# Amplifier.net
KiCad netlist of a schematic drawn in Altium Designer
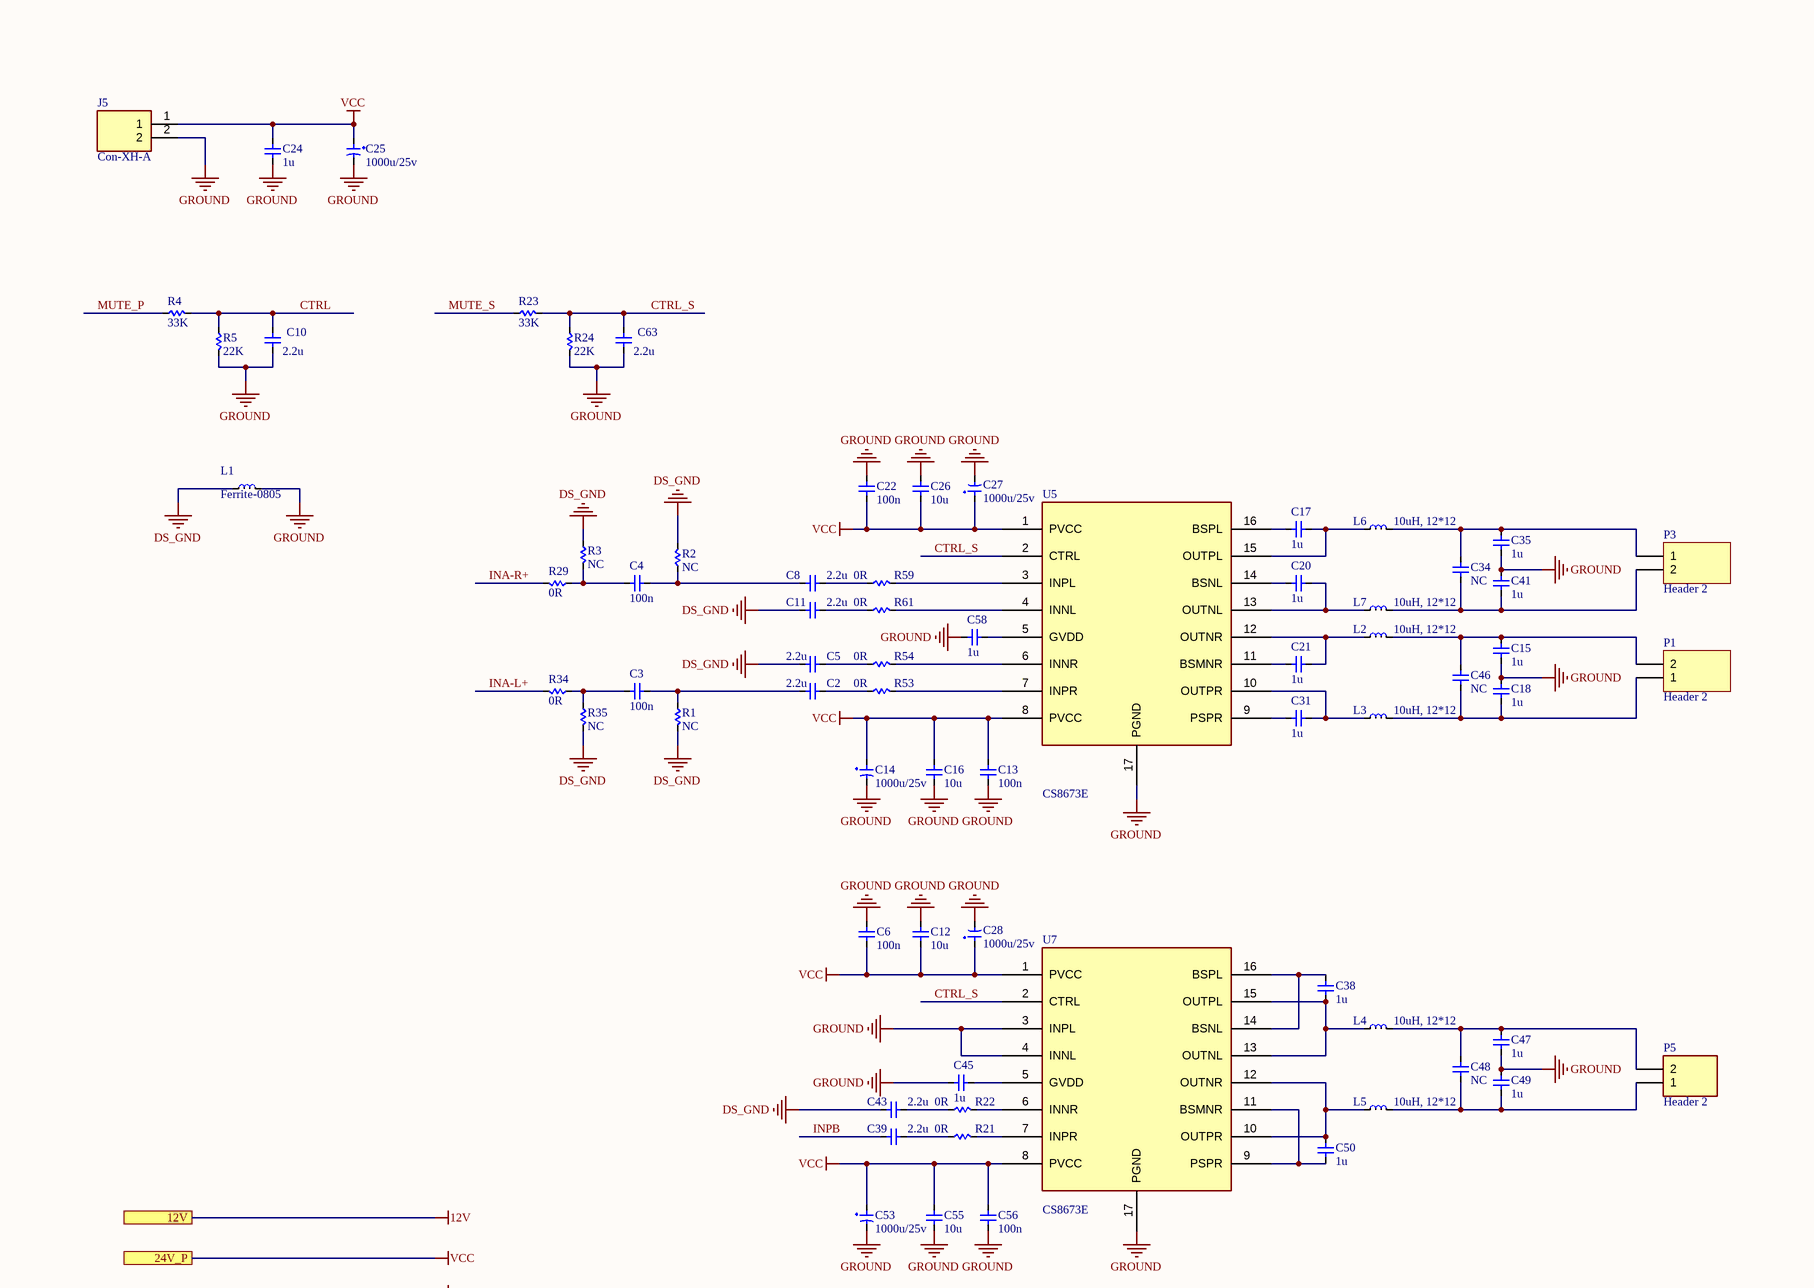
[diagram p0: Amplifier.SchDoc, top left]
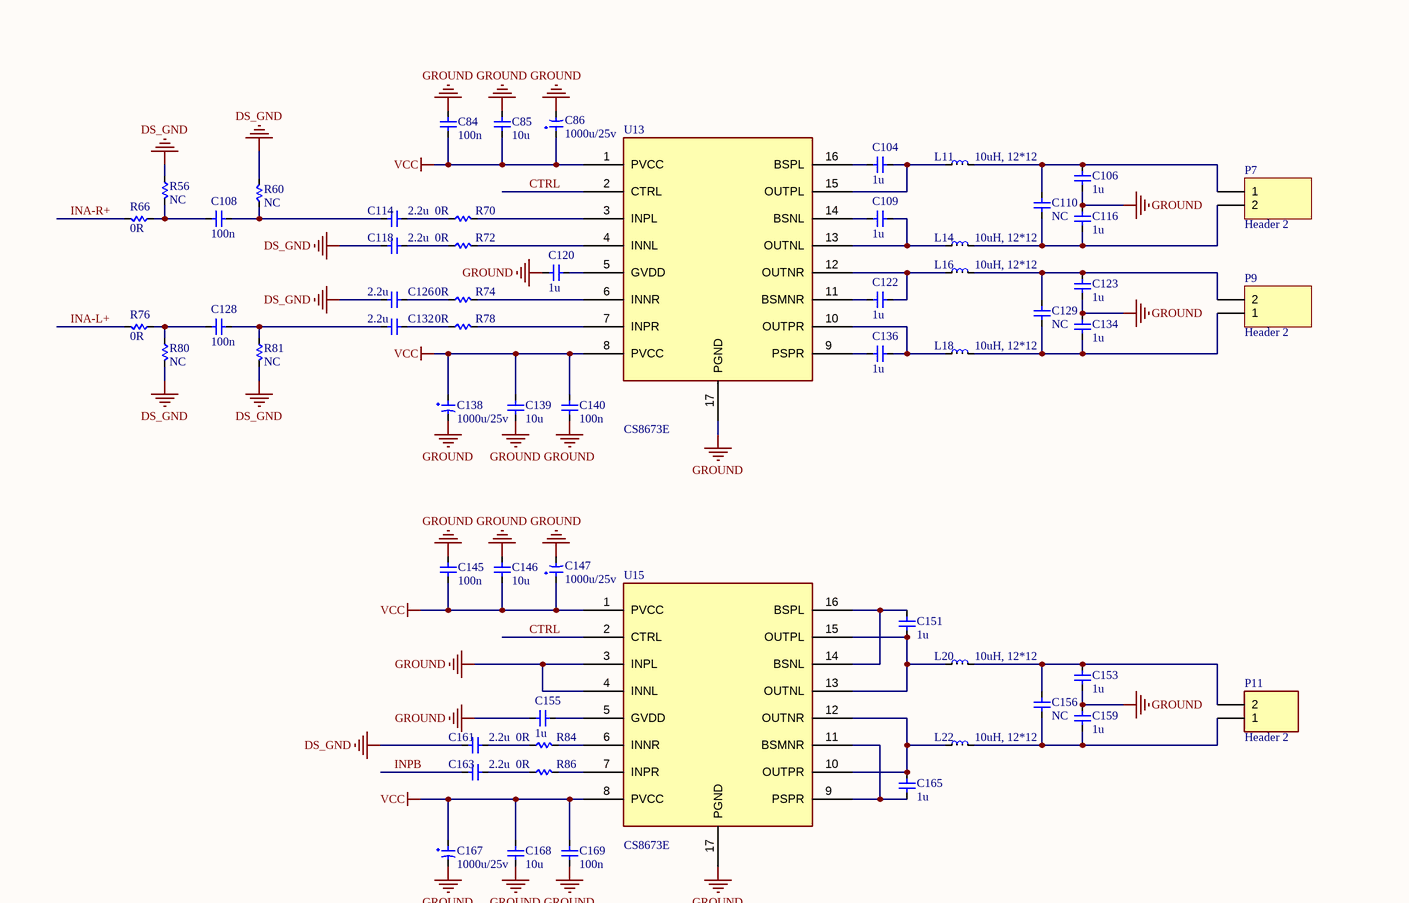
[diagram p1: Amplifier.SchDoc, top middle]
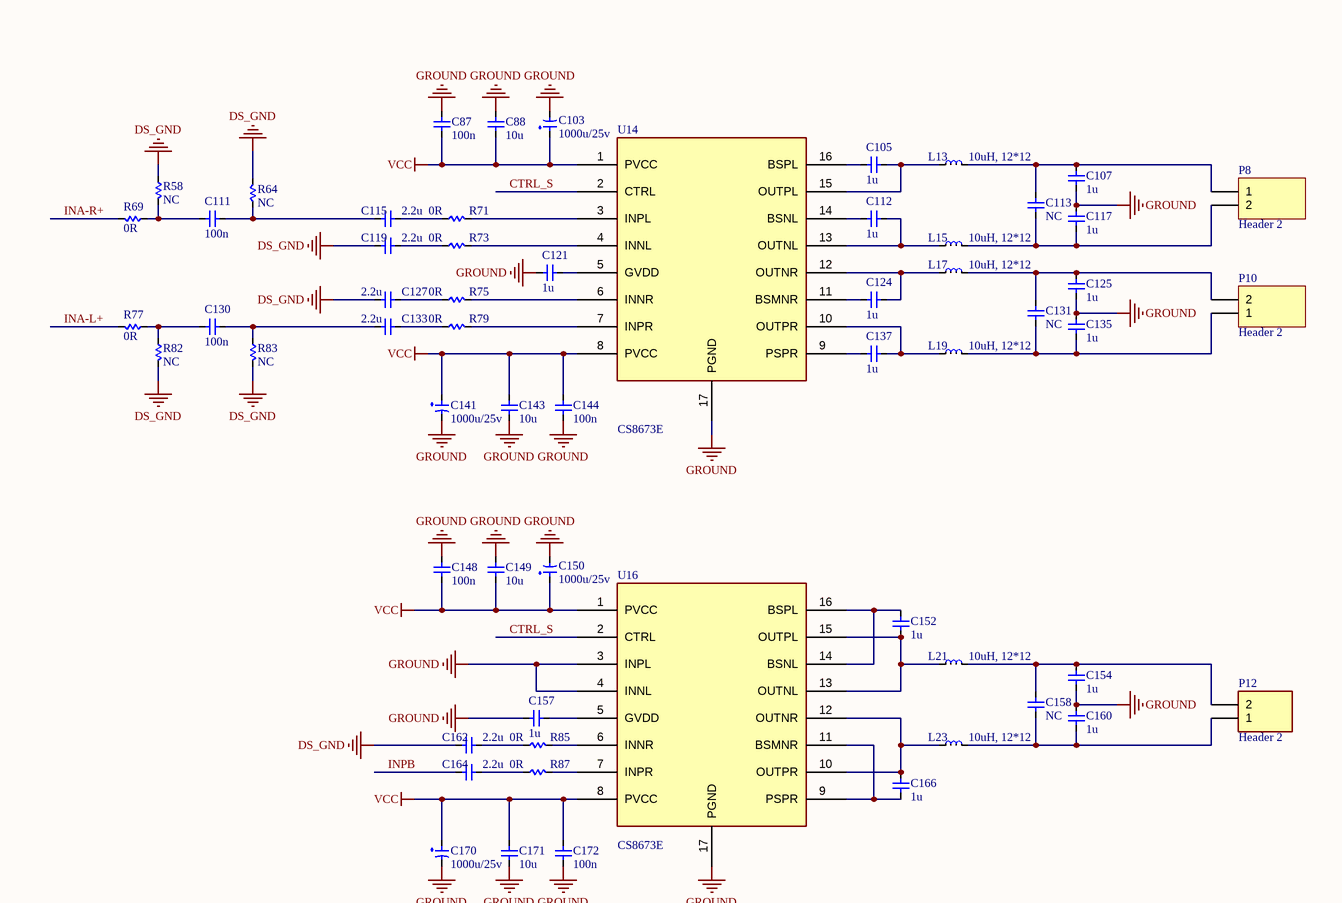
[diagram p2: Amplifier.SchDoc, top right]
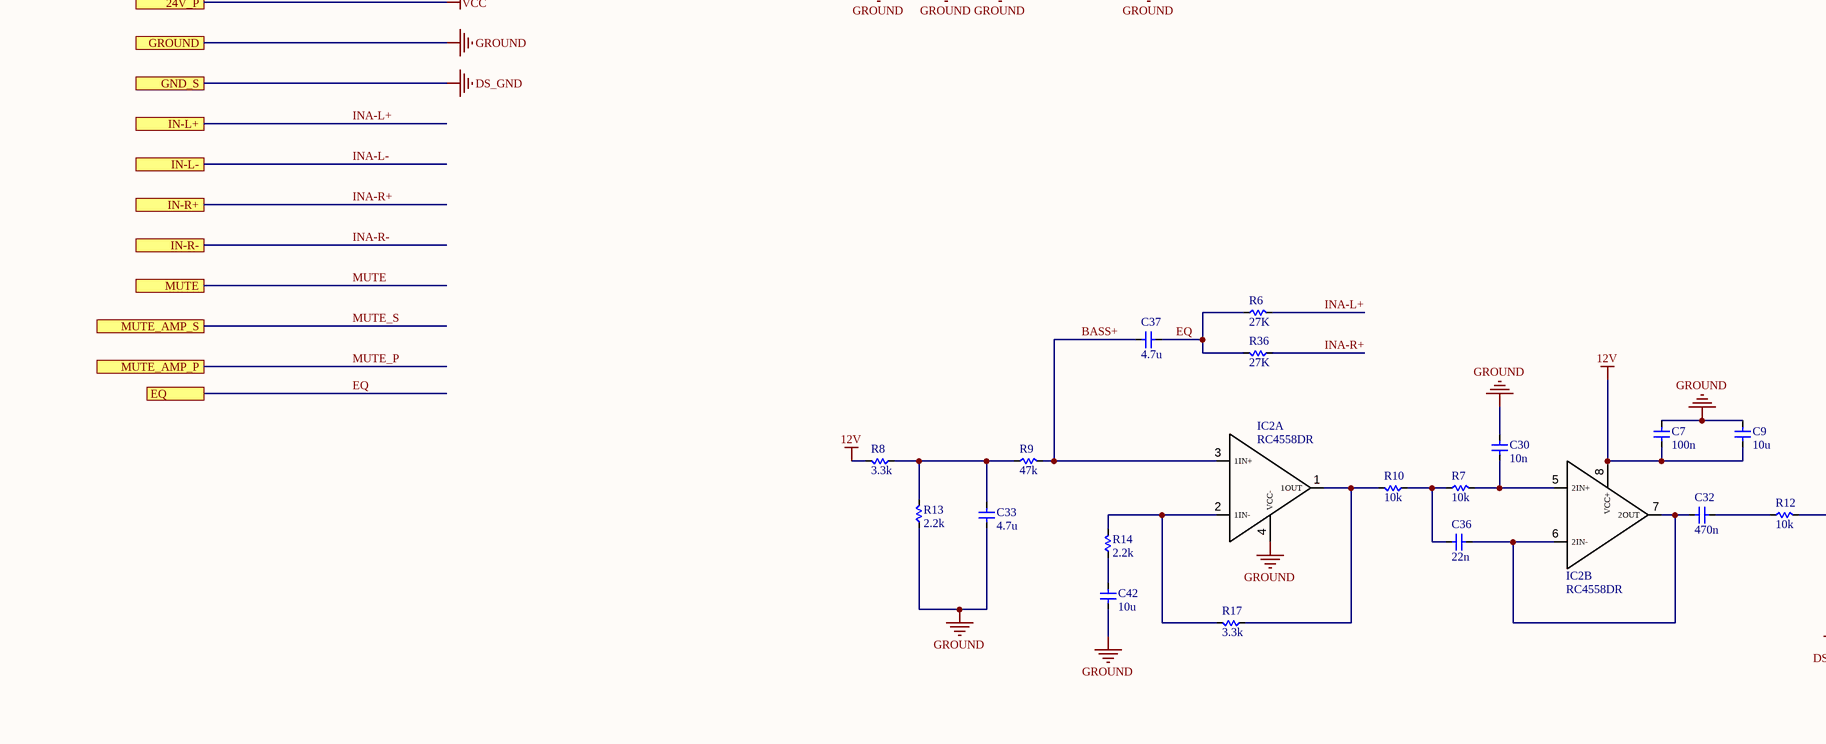
[diagram p3: Amplifier.SchDoc, bottom left]
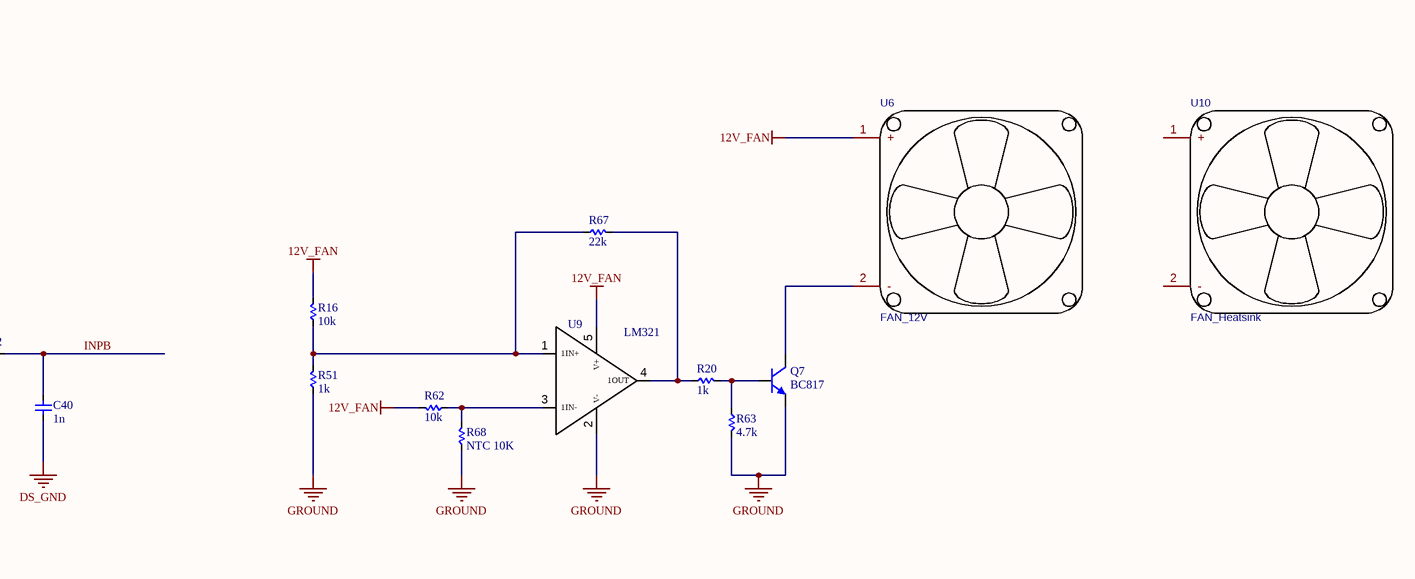
[diagram p4: Amplifier.SchDoc, bottom middle]

(export (version "E")
  (design (tool "Eeschema 10.0.6"))
  (components
    (comp (ref "C2")
      (value "2.2u")
      (footprint "cap0603")
      (description "Capacitor 0603")
      (fields (field (name "PUBLISHER") "Altium Limited"))
      (libsource (lib "mylib1") (part "Cap 0603"))
    )
    (comp (ref "C3")
      (value "100n")
      (footprint "cap0603")
      (description "Capacitor 0603")
      (fields (field (name "PUBLISHER") "Altium Limited"))
      (libsource (lib "mylib") (part "Cap 0603"))
    )
    (comp (ref "C4")
      (value "100n")
      (footprint "cap0603")
      (description "Capacitor 0603")
      (fields (field (name "PUBLISHER") "Altium Limited"))
      (libsource (lib "mylib") (part "Cap 0603"))
    )
    (comp (ref "C5")
      (value "2.2u")
      (footprint "cap0603")
      (description "Capacitor 0603")
      (fields (field (name "PUBLISHER") "Altium Limited"))
      (libsource (lib "mylib1") (part "Cap 0603"))
    )
    (comp (ref "C6")
      (value "100n")
      (footprint "cap0603")
      (description "Capacitor 0603")
      (fields (field (name "PUBLISHER") "Altium Limited"))
      (libsource (lib "mylib1") (part "Cap 0603"))
    )
    (comp (ref "C7")
      (value "100n")
      (footprint "cap0603")
      (description "Capacitor 0603")
      (fields (field (name "PUBLISHER") "Altium Limited"))
      (libsource (lib "mylib1") (part "Cap 0603"))
    )
    (comp (ref "C8")
      (value "2.2u")
      (footprint "cap0603")
      (description "Capacitor 0603")
      (fields (field (name "PUBLISHER") "Altium Limited"))
      (libsource (lib "mylib1") (part "Cap 0603"))
    )
    (comp (ref "C9")
      (value "10u")
      (footprint "cap0603")
      (description "Capacitor 0603")
      (fields (field (name "PUBLISHER") "Altium Limited"))
      (libsource (lib "mylib") (part "Cap 0603"))
    )
    (comp (ref "C10")
      (value "2.2u")
      (footprint "cap0603")
      (description "Capacitor 0603")
      (fields (field (name "PUBLISHER") "Altium Limited"))
      (libsource (lib "mylib") (part "Cap 0603"))
    )
    (comp (ref "C11")
      (value "2.2u")
      (footprint "cap0603")
      (description "Capacitor 0603")
      (fields (field (name "PUBLISHER") "Altium Limited"))
      (libsource (lib "mylib1") (part "Cap 0603"))
    )
    (comp (ref "C12")
      (value "10u")
      (footprint "CAP 0805")
      (description "Capacitor 0805")
      (fields (field (name "PUBLISHER") "Altium Limited"))
      (libsource (lib "Amin-Library") (part "Cap 0805"))
    )
    (comp (ref "C13")
      (value "100n")
      (footprint "cap0603")
      (description "Capacitor 0603")
      (fields (field (name "PUBLISHER") "Altium Limited"))
      (libsource (lib "mylib1") (part "Cap 0603"))
    )
    (comp (ref "C14")
      (value "1000u/25v")
      (footprint "CAP DIP 10*13")
      (description "2200ÂµF 50V Aluminum Electrolytic Capacitors Radial, Can 1000 Hrs @ 105Â°C")
      (fields (field (name "MF") "Nichicon") (field (name "MP") "UVZ1H222MHD"))
      (libsource (lib "") (part "capacitor dip 10*13_1"))
    )
    (comp (ref "C15")
      (value "1u")
      (footprint "CAP 0805")
      (description "Capacitor 0805")
      (fields (field (name "PUBLISHER") "Altium Limited"))
      (libsource (lib "Amin-Library") (part "Cap 0805"))
    )
    (comp (ref "C16")
      (value "10u")
      (footprint "CAP 0805")
      (description "Capacitor 0805")
      (fields (field (name "PUBLISHER") "Altium Limited"))
      (libsource (lib "Amin-Library") (part "Cap 0805"))
    )
    (comp (ref "C17")
      (value "1u")
      (footprint "CAP 0805")
      (description "Capacitor 0805")
      (fields (field (name "PUBLISHER") "Altium Limited"))
      (libsource (lib "Amin-Library") (part "Cap 0805"))
    )
    (comp (ref "C18")
      (value "1u")
      (footprint "CAP 0805")
      (description "Capacitor 0805")
      (fields (field (name "PUBLISHER") "Altium Limited"))
      (libsource (lib "Amin-Library") (part "Cap 0805"))
    )
    (comp (ref "C20")
      (value "1u")
      (footprint "CAP 0805")
      (description "Capacitor 0805")
      (fields (field (name "PUBLISHER") "Altium Limited"))
      (libsource (lib "Amin-Library") (part "Cap 0805"))
    )
    (comp (ref "C21")
      (value "1u")
      (footprint "CAP 0805")
      (description "Capacitor 0805")
      (fields (field (name "PUBLISHER") "Altium Limited"))
      (libsource (lib "Amin-Library") (part "Cap 0805"))
    )
    (comp (ref "C22")
      (value "100n")
      (footprint "cap0603")
      (description "Capacitor 0603")
      (fields (field (name "PUBLISHER") "Altium Limited"))
      (libsource (lib "mylib1") (part "Cap 0603"))
    )
    (comp (ref "C24")
      (value "1u")
      (footprint "cap0603")
      (description "Capacitor 0603")
      (fields (field (name "PUBLISHER") "Altium Limited"))
      (libsource (lib "mylib1") (part "Cap 0603"))
    )
    (comp (ref "C25")
      (value "1000u/25v")
      (footprint "CAP DIP 10*13")
      (description "2200ÂµF 50V Aluminum Electrolytic Capacitors Radial, Can 1000 Hrs @ 105Â°C")
      (fields (field (name "MF") "Nichicon") (field (name "MP") "UVZ1H222MHD"))
      (libsource (lib "") (part "capacitor dip 10*13_2"))
    )
    (comp (ref "C26")
      (value "10u")
      (footprint "CAP 0805")
      (description "Capacitor 0805")
      (fields (field (name "PUBLISHER") "Altium Limited"))
      (libsource (lib "Amin-Library") (part "Cap 0805"))
    )
    (comp (ref "C27")
      (value "1000u/25v")
      (footprint "CAP DIP 10*13")
      (description "2200ÂµF 50V Aluminum Electrolytic Capacitors Radial, Can 1000 Hrs @ 105Â°C")
      (fields (field (name "MF") "Nichicon") (field (name "MP") "UVZ1H222MHD"))
      (libsource (lib "mylib1") (part "capacitor dip 10*13"))
    )
    (comp (ref "C28")
      (value "1000u/25v")
      (footprint "CAP DIP 10*13")
      (description "2200ÂµF 50V Aluminum Electrolytic Capacitors Radial, Can 1000 Hrs @ 105Â°C")
      (fields (field (name "MF") "Nichicon") (field (name "MP") "UVZ1H222MHD"))
      (libsource (lib "mylib1") (part "capacitor dip 10*13"))
    )
    (comp (ref "C30")
      (value "10n")
      (footprint "cap0603")
      (description "Capacitor 0603")
      (fields (field (name "PUBLISHER") "Altium Limited"))
      (libsource (lib "mylib1") (part "Cap 0603"))
    )
    (comp (ref "C31")
      (value "1u")
      (footprint "CAP 0805")
      (description "Capacitor 0805")
      (fields (field (name "PUBLISHER") "Altium Limited"))
      (libsource (lib "Amin-Library") (part "Cap 0805"))
    )
    (comp (ref "C32")
      (value "470n")
      (footprint "cap0603")
      (description "Capacitor 0603")
      (fields (field (name "PUBLISHER") "Altium Limited"))
      (libsource (lib "mylib1") (part "Cap 0603"))
    )
    (comp (ref "C33")
      (value "4.7u")
      (footprint "cap0603")
      (description "Capacitor 0603")
      (fields (field (name "PUBLISHER") "Altium Limited"))
      (libsource (lib "mylib") (part "Cap 0603"))
    )
    (comp (ref "C34")
      (value "NC")
      (footprint "CAP 0805")
      (description "Capacitor 0805")
      (fields (field (name "PUBLISHER") "Altium Limited"))
      (libsource (lib "Amin-Library") (part "Cap 0805"))
    )
    (comp (ref "C35")
      (value "1u")
      (footprint "CAP 0805")
      (description "Capacitor 0805")
      (fields (field (name "PUBLISHER") "Altium Limited"))
      (libsource (lib "Amin-Library") (part "Cap 0805"))
    )
    (comp (ref "C36")
      (value "22n")
      (footprint "cap0603")
      (description "Capacitor 0603")
      (fields (field (name "PUBLISHER") "Altium Limited"))
      (libsource (lib "mylib1") (part "Cap 0603"))
    )
    (comp (ref "C37")
      (value "4.7u")
      (footprint "cap0603")
      (description "Capacitor 0603")
      (fields (field (name "PUBLISHER") "Altium Limited"))
      (libsource (lib "mylib") (part "Cap 0603"))
    )
    (comp (ref "C38")
      (value "1u")
      (footprint "CAP 0805")
      (description "Capacitor 0805")
      (fields (field (name "PUBLISHER") "Altium Limited"))
      (libsource (lib "Amin-Library") (part "Cap 0805"))
    )
    (comp (ref "C39")
      (value "2.2u")
      (footprint "cap0603")
      (description "Capacitor 0603")
      (fields (field (name "PUBLISHER") "Altium Limited"))
      (libsource (lib "mylib1") (part "Cap 0603"))
    )
    (comp (ref "C40")
      (value "1n")
      (footprint "cap0603")
      (description "Capacitor 0603")
      (fields (field (name "PUBLISHER") "Altium Limited"))
      (libsource (lib "mylib1") (part "Cap 0603"))
    )
    (comp (ref "C41")
      (value "1u")
      (footprint "CAP 0805")
      (description "Capacitor 0805")
      (fields (field (name "PUBLISHER") "Altium Limited"))
      (libsource (lib "Amin-Library") (part "Cap 0805"))
    )
    (comp (ref "C42")
      (value "10u")
      (footprint "CAP 1206")
      (description "Capacitor 1206")
      (fields (field (name "PUBLISHER") "Altium Limited"))
      (libsource (lib "mylib") (part "Cap 1206"))
    )
    (comp (ref "C43")
      (value "2.2u")
      (footprint "cap0603")
      (description "Capacitor 0603")
      (fields (field (name "PUBLISHER") "Altium Limited"))
      (libsource (lib "mylib1") (part "Cap 0603"))
    )
    (comp (ref "C45")
      (value "1u")
      (footprint "cap0603")
      (description "Capacitor 0603")
      (fields (field (name "PUBLISHER") "Altium Limited"))
      (libsource (lib "mylib1") (part "Cap 0603"))
    )
    (comp (ref "C46")
      (value "NC")
      (footprint "CAP 0805")
      (description "Capacitor 0805")
      (fields (field (name "PUBLISHER") "Altium Limited"))
      (libsource (lib "Amin-Library") (part "Cap 0805"))
    )
    (comp (ref "C47")
      (value "1u")
      (footprint "CAP 0805")
      (description "Capacitor 0805")
      (fields (field (name "PUBLISHER") "Altium Limited"))
      (libsource (lib "Amin-Library") (part "Cap 0805"))
    )
    (comp (ref "C48")
      (value "NC")
      (footprint "CAP 0805")
      (description "Capacitor 0805")
      (fields (field (name "PUBLISHER") "Altium Limited"))
      (libsource (lib "Amin-Library") (part "Cap 0805"))
    )
    (comp (ref "C49")
      (value "1u")
      (footprint "CAP 0805")
      (description "Capacitor 0805")
      (fields (field (name "PUBLISHER") "Altium Limited"))
      (libsource (lib "Amin-Library") (part "Cap 0805"))
    )
    (comp (ref "C50")
      (value "1u")
      (footprint "CAP 0805")
      (description "Capacitor 0805")
      (fields (field (name "PUBLISHER") "Altium Limited"))
      (libsource (lib "Amin-Library") (part "Cap 0805"))
    )
    (comp (ref "C53")
      (value "1000u/25v")
      (footprint "CAP DIP 10*13")
      (description "2200ÂµF 50V Aluminum Electrolytic Capacitors Radial, Can 1000 Hrs @ 105Â°C")
      (fields (field (name "MF") "Nichicon") (field (name "MP") "UVZ1H222MHD"))
      (libsource (lib "") (part "capacitor dip 10*13_1"))
    )
    (comp (ref "C55")
      (value "10u")
      (footprint "CAP 0805")
      (description "Capacitor 0805")
      (fields (field (name "PUBLISHER") "Altium Limited"))
      (libsource (lib "Amin-Library") (part "Cap 0805"))
    )
    (comp (ref "C56")
      (value "100n")
      (footprint "cap0603")
      (description "Capacitor 0603")
      (fields (field (name "PUBLISHER") "Altium Limited"))
      (libsource (lib "mylib1") (part "Cap 0603"))
    )
    (comp (ref "C58")
      (value "1u")
      (footprint "cap0603")
      (description "Capacitor 0603")
      (fields (field (name "PUBLISHER") "Altium Limited"))
      (libsource (lib "mylib1") (part "Cap 0603"))
    )
    (comp (ref "C63")
      (value "2.2u")
      (footprint "cap0603")
      (description "Capacitor 0603")
      (fields (field (name "PUBLISHER") "Altium Limited"))
      (libsource (lib "mylib") (part "Cap 0603"))
    )
    (comp (ref "C84")
      (value "100n")
      (footprint "cap0603")
      (description "Capacitor 0603")
      (fields (field (name "PUBLISHER") "Altium Limited"))
      (libsource (lib "mylib1") (part "Cap 0603"))
    )
    (comp (ref "C85")
      (value "10u")
      (footprint "CAP 0805")
      (description "Capacitor 0805")
      (fields (field (name "PUBLISHER") "Altium Limited"))
      (libsource (lib "Amin-Library") (part "Cap 0805"))
    )
    (comp (ref "C86")
      (value "1000u/25v")
      (footprint "CAP DIP 10*13")
      (description "2200ÂµF 50V Aluminum Electrolytic Capacitors Radial, Can 1000 Hrs @ 105Â°C")
      (fields (field (name "MF") "Nichicon") (field (name "MP") "UVZ1H222MHD"))
      (libsource (lib "mylib1") (part "capacitor dip 10*13"))
    )
    (comp (ref "C87")
      (value "100n")
      (footprint "cap0603")
      (description "Capacitor 0603")
      (fields (field (name "PUBLISHER") "Altium Limited"))
      (libsource (lib "mylib1") (part "Cap 0603"))
    )
    (comp (ref "C88")
      (value "10u")
      (footprint "CAP 0805")
      (description "Capacitor 0805")
      (fields (field (name "PUBLISHER") "Altium Limited"))
      (libsource (lib "Amin-Library") (part "Cap 0805"))
    )
    (comp (ref "C103")
      (value "1000u/25v")
      (footprint "CAP DIP 10*13")
      (description "2200ÂµF 50V Aluminum Electrolytic Capacitors Radial, Can 1000 Hrs @ 105Â°C")
      (fields (field (name "MF") "Nichicon") (field (name "MP") "UVZ1H222MHD"))
      (libsource (lib "mylib1") (part "capacitor dip 10*13"))
    )
    (comp (ref "C104")
      (value "1u")
      (footprint "CAP 0805")
      (description "Capacitor 0805")
      (fields (field (name "PUBLISHER") "Altium Limited"))
      (libsource (lib "Amin-Library") (part "Cap 0805"))
    )
    (comp (ref "C105")
      (value "1u")
      (footprint "CAP 0805")
      (description "Capacitor 0805")
      (fields (field (name "PUBLISHER") "Altium Limited"))
      (libsource (lib "Amin-Library") (part "Cap 0805"))
    )
    (comp (ref "C106")
      (value "1u")
      (footprint "CAP 0805")
      (description "Capacitor 0805")
      (fields (field (name "PUBLISHER") "Altium Limited"))
      (libsource (lib "Amin-Library") (part "Cap 0805"))
    )
    (comp (ref "C107")
      (value "1u")
      (footprint "CAP 0805")
      (description "Capacitor 0805")
      (fields (field (name "PUBLISHER") "Altium Limited"))
      (libsource (lib "Amin-Library") (part "Cap 0805"))
    )
    (comp (ref "C108")
      (value "100n")
      (footprint "cap0603")
      (description "Capacitor 0603")
      (fields (field (name "PUBLISHER") "Altium Limited"))
      (libsource (lib "mylib") (part "Cap 0603"))
    )
    (comp (ref "C109")
      (value "1u")
      (footprint "CAP 0805")
      (description "Capacitor 0805")
      (fields (field (name "PUBLISHER") "Altium Limited"))
      (libsource (lib "Amin-Library") (part "Cap 0805"))
    )
    (comp (ref "C110")
      (value "NC")
      (footprint "CAP 0805")
      (description "Capacitor 0805")
      (fields (field (name "PUBLISHER") "Altium Limited"))
      (libsource (lib "Amin-Library") (part "Cap 0805"))
    )
    (comp (ref "C111")
      (value "100n")
      (footprint "cap0603")
      (description "Capacitor 0603")
      (fields (field (name "PUBLISHER") "Altium Limited"))
      (libsource (lib "mylib") (part "Cap 0603"))
    )
    (comp (ref "C112")
      (value "1u")
      (footprint "CAP 0805")
      (description "Capacitor 0805")
      (fields (field (name "PUBLISHER") "Altium Limited"))
      (libsource (lib "Amin-Library") (part "Cap 0805"))
    )
    (comp (ref "C113")
      (value "NC")
      (footprint "CAP 0805")
      (description "Capacitor 0805")
      (fields (field (name "PUBLISHER") "Altium Limited"))
      (libsource (lib "Amin-Library") (part "Cap 0805"))
    )
    (comp (ref "C114")
      (value "2.2u")
      (footprint "cap0603")
      (description "Capacitor 0603")
      (fields (field (name "PUBLISHER") "Altium Limited"))
      (libsource (lib "mylib1") (part "Cap 0603"))
    )
    (comp (ref "C115")
      (value "2.2u")
      (footprint "cap0603")
      (description "Capacitor 0603")
      (fields (field (name "PUBLISHER") "Altium Limited"))
      (libsource (lib "mylib1") (part "Cap 0603"))
    )
    (comp (ref "C116")
      (value "1u")
      (footprint "CAP 0805")
      (description "Capacitor 0805")
      (fields (field (name "PUBLISHER") "Altium Limited"))
      (libsource (lib "Amin-Library") (part "Cap 0805"))
    )
    (comp (ref "C117")
      (value "1u")
      (footprint "CAP 0805")
      (description "Capacitor 0805")
      (fields (field (name "PUBLISHER") "Altium Limited"))
      (libsource (lib "Amin-Library") (part "Cap 0805"))
    )
    (comp (ref "C118")
      (value "2.2u")
      (footprint "cap0603")
      (description "Capacitor 0603")
      (fields (field (name "PUBLISHER") "Altium Limited"))
      (libsource (lib "mylib1") (part "Cap 0603"))
    )
    (comp (ref "C119")
      (value "2.2u")
      (footprint "cap0603")
      (description "Capacitor 0603")
      (fields (field (name "PUBLISHER") "Altium Limited"))
      (libsource (lib "mylib1") (part "Cap 0603"))
    )
    (comp (ref "C120")
      (value "1u")
      (footprint "cap0603")
      (description "Capacitor 0603")
      (fields (field (name "PUBLISHER") "Altium Limited"))
      (libsource (lib "mylib1") (part "Cap 0603"))
    )
    (comp (ref "C121")
      (value "1u")
      (footprint "cap0603")
      (description "Capacitor 0603")
      (fields (field (name "PUBLISHER") "Altium Limited"))
      (libsource (lib "mylib1") (part "Cap 0603"))
    )
    (comp (ref "C122")
      (value "1u")
      (footprint "CAP 0805")
      (description "Capacitor 0805")
      (fields (field (name "PUBLISHER") "Altium Limited"))
      (libsource (lib "Amin-Library") (part "Cap 0805"))
    )
    (comp (ref "C123")
      (value "1u")
      (footprint "CAP 0805")
      (description "Capacitor 0805")
      (fields (field (name "PUBLISHER") "Altium Limited"))
      (libsource (lib "Amin-Library") (part "Cap 0805"))
    )
    (comp (ref "C124")
      (value "1u")
      (footprint "CAP 0805")
      (description "Capacitor 0805")
      (fields (field (name "PUBLISHER") "Altium Limited"))
      (libsource (lib "Amin-Library") (part "Cap 0805"))
    )
    (comp (ref "C125")
      (value "1u")
      (footprint "CAP 0805")
      (description "Capacitor 0805")
      (fields (field (name "PUBLISHER") "Altium Limited"))
      (libsource (lib "Amin-Library") (part "Cap 0805"))
    )
    (comp (ref "C126")
      (value "2.2u")
      (footprint "cap0603")
      (description "Capacitor 0603")
      (fields (field (name "PUBLISHER") "Altium Limited"))
      (libsource (lib "mylib1") (part "Cap 0603"))
    )
    (comp (ref "C127")
      (value "2.2u")
      (footprint "cap0603")
      (description "Capacitor 0603")
      (fields (field (name "PUBLISHER") "Altium Limited"))
      (libsource (lib "mylib1") (part "Cap 0603"))
    )
    (comp (ref "C128")
      (value "100n")
      (footprint "cap0603")
      (description "Capacitor 0603")
      (fields (field (name "PUBLISHER") "Altium Limited"))
      (libsource (lib "mylib") (part "Cap 0603"))
    )
    (comp (ref "C129")
      (value "NC")
      (footprint "CAP 0805")
      (description "Capacitor 0805")
      (fields (field (name "PUBLISHER") "Altium Limited"))
      (libsource (lib "Amin-Library") (part "Cap 0805"))
    )
    (comp (ref "C130")
      (value "100n")
      (footprint "cap0603")
      (description "Capacitor 0603")
      (fields (field (name "PUBLISHER") "Altium Limited"))
      (libsource (lib "mylib") (part "Cap 0603"))
    )
    (comp (ref "C131")
      (value "NC")
      (footprint "CAP 0805")
      (description "Capacitor 0805")
      (fields (field (name "PUBLISHER") "Altium Limited"))
      (libsource (lib "Amin-Library") (part "Cap 0805"))
    )
    (comp (ref "C132")
      (value "2.2u")
      (footprint "cap0603")
      (description "Capacitor 0603")
      (fields (field (name "PUBLISHER") "Altium Limited"))
      (libsource (lib "mylib1") (part "Cap 0603"))
    )
    (comp (ref "C133")
      (value "2.2u")
      (footprint "cap0603")
      (description "Capacitor 0603")
      (fields (field (name "PUBLISHER") "Altium Limited"))
      (libsource (lib "mylib1") (part "Cap 0603"))
    )
    (comp (ref "C134")
      (value "1u")
      (footprint "CAP 0805")
      (description "Capacitor 0805")
      (fields (field (name "PUBLISHER") "Altium Limited"))
      (libsource (lib "Amin-Library") (part "Cap 0805"))
    )
    (comp (ref "C135")
      (value "1u")
      (footprint "CAP 0805")
      (description "Capacitor 0805")
      (fields (field (name "PUBLISHER") "Altium Limited"))
      (libsource (lib "Amin-Library") (part "Cap 0805"))
    )
    (comp (ref "C136")
      (value "1u")
      (footprint "CAP 0805")
      (description "Capacitor 0805")
      (fields (field (name "PUBLISHER") "Altium Limited"))
      (libsource (lib "Amin-Library") (part "Cap 0805"))
    )
    (comp (ref "C137")
      (value "1u")
      (footprint "CAP 0805")
      (description "Capacitor 0805")
      (fields (field (name "PUBLISHER") "Altium Limited"))
      (libsource (lib "Amin-Library") (part "Cap 0805"))
    )
    (comp (ref "C138")
      (value "1000u/25v")
      (footprint "CAP DIP 10*13")
      (description "2200ÂµF 50V Aluminum Electrolytic Capacitors Radial, Can 1000 Hrs @ 105Â°C")
      (fields (field (name "MF") "Nichicon") (field (name "MP") "UVZ1H222MHD"))
      (libsource (lib "") (part "capacitor dip 10*13_1"))
    )
    (comp (ref "C139")
      (value "10u")
      (footprint "CAP 0805")
      (description "Capacitor 0805")
      (fields (field (name "PUBLISHER") "Altium Limited"))
      (libsource (lib "Amin-Library") (part "Cap 0805"))
    )
    (comp (ref "C140")
      (value "100n")
      (footprint "cap0603")
      (description "Capacitor 0603")
      (fields (field (name "PUBLISHER") "Altium Limited"))
      (libsource (lib "mylib1") (part "Cap 0603"))
    )
    (comp (ref "C141")
      (value "1000u/25v")
      (footprint "CAP DIP 10*13")
      (description "2200ÂµF 50V Aluminum Electrolytic Capacitors Radial, Can 1000 Hrs @ 105Â°C")
      (fields (field (name "MF") "Nichicon") (field (name "MP") "UVZ1H222MHD"))
      (libsource (lib "") (part "capacitor dip 10*13_1"))
    )
    (comp (ref "C143")
      (value "10u")
      (footprint "CAP 0805")
      (description "Capacitor 0805")
      (fields (field (name "PUBLISHER") "Altium Limited"))
      (libsource (lib "Amin-Library") (part "Cap 0805"))
    )
    (comp (ref "C144")
      (value "100n")
      (footprint "cap0603")
      (description "Capacitor 0603")
      (fields (field (name "PUBLISHER") "Altium Limited"))
      (libsource (lib "mylib1") (part "Cap 0603"))
    )
    (comp (ref "C145")
      (value "100n")
      (footprint "cap0603")
      (description "Capacitor 0603")
      (fields (field (name "PUBLISHER") "Altium Limited"))
      (libsource (lib "mylib1") (part "Cap 0603"))
    )
    (comp (ref "C146")
      (value "10u")
      (footprint "CAP 0805")
      (description "Capacitor 0805")
      (fields (field (name "PUBLISHER") "Altium Limited"))
      (libsource (lib "Amin-Library") (part "Cap 0805"))
    )
    (comp (ref "C147")
      (value "1000u/25v")
      (footprint "CAP DIP 10*13")
      (description "2200ÂµF 50V Aluminum Electrolytic Capacitors Radial, Can 1000 Hrs @ 105Â°C")
      (fields (field (name "MF") "Nichicon") (field (name "MP") "UVZ1H222MHD"))
      (libsource (lib "mylib1") (part "capacitor dip 10*13"))
    )
    (comp (ref "C148")
      (value "100n")
      (footprint "cap0603")
      (description "Capacitor 0603")
      (fields (field (name "PUBLISHER") "Altium Limited"))
      (libsource (lib "mylib1") (part "Cap 0603"))
    )
    (comp (ref "C149")
      (value "10u")
      (footprint "CAP 0805")
      (description "Capacitor 0805")
      (fields (field (name "PUBLISHER") "Altium Limited"))
      (libsource (lib "Amin-Library") (part "Cap 0805"))
    )
    (comp (ref "C150")
      (value "1000u/25v")
      (footprint "CAP DIP 10*13")
      (description "2200ÂµF 50V Aluminum Electrolytic Capacitors Radial, Can 1000 Hrs @ 105Â°C")
      (fields (field (name "MF") "Nichicon") (field (name "MP") "UVZ1H222MHD"))
      (libsource (lib "mylib1") (part "capacitor dip 10*13"))
    )
    (comp (ref "C151")
      (value "1u")
      (footprint "CAP 0805")
      (description "Capacitor 0805")
      (fields (field (name "PUBLISHER") "Altium Limited"))
      (libsource (lib "Amin-Library") (part "Cap 0805"))
    )
    (comp (ref "C152")
      (value "1u")
      (footprint "CAP 0805")
      (description "Capacitor 0805")
      (fields (field (name "PUBLISHER") "Altium Limited"))
      (libsource (lib "Amin-Library") (part "Cap 0805"))
    )
    (comp (ref "C153")
      (value "1u")
      (footprint "CAP 0805")
      (description "Capacitor 0805")
      (fields (field (name "PUBLISHER") "Altium Limited"))
      (libsource (lib "Amin-Library") (part "Cap 0805"))
    )
    (comp (ref "C154")
      (value "1u")
      (footprint "CAP 0805")
      (description "Capacitor 0805")
      (fields (field (name "PUBLISHER") "Altium Limited"))
      (libsource (lib "Amin-Library") (part "Cap 0805"))
    )
    (comp (ref "C155")
      (value "1u")
      (footprint "cap0603")
      (description "Capacitor 0603")
      (fields (field (name "PUBLISHER") "Altium Limited"))
      (libsource (lib "mylib1") (part "Cap 0603"))
    )
    (comp (ref "C156")
      (value "NC")
      (footprint "CAP 0805")
      (description "Capacitor 0805")
      (fields (field (name "PUBLISHER") "Altium Limited"))
      (libsource (lib "Amin-Library") (part "Cap 0805"))
    )
    (comp (ref "C157")
      (value "1u")
      (footprint "cap0603")
      (description "Capacitor 0603")
      (fields (field (name "PUBLISHER") "Altium Limited"))
      (libsource (lib "mylib1") (part "Cap 0603"))
    )
    (comp (ref "C158")
      (value "NC")
      (footprint "CAP 0805")
      (description "Capacitor 0805")
      (fields (field (name "PUBLISHER") "Altium Limited"))
      (libsource (lib "Amin-Library") (part "Cap 0805"))
    )
    (comp (ref "C159")
      (value "1u")
      (footprint "CAP 0805")
      (description "Capacitor 0805")
      (fields (field (name "PUBLISHER") "Altium Limited"))
      (libsource (lib "Amin-Library") (part "Cap 0805"))
    )
    (comp (ref "C160")
      (value "1u")
      (footprint "CAP 0805")
      (description "Capacitor 0805")
      (fields (field (name "PUBLISHER") "Altium Limited"))
      (libsource (lib "Amin-Library") (part "Cap 0805"))
    )
    (comp (ref "C161")
      (value "2.2u")
      (footprint "cap0603")
      (description "Capacitor 0603")
      (fields (field (name "PUBLISHER") "Altium Limited"))
      (libsource (lib "mylib1") (part "Cap 0603"))
    )
    (comp (ref "C162")
      (value "2.2u")
      (footprint "cap0603")
      (description "Capacitor 0603")
      (fields (field (name "PUBLISHER") "Altium Limited"))
      (libsource (lib "mylib1") (part "Cap 0603"))
    )
    (comp (ref "C163")
      (value "2.2u")
      (footprint "cap0603")
      (description "Capacitor 0603")
      (fields (field (name "PUBLISHER") "Altium Limited"))
      (libsource (lib "mylib1") (part "Cap 0603"))
    )
    (comp (ref "C164")
      (value "2.2u")
      (footprint "cap0603")
      (description "Capacitor 0603")
      (fields (field (name "PUBLISHER") "Altium Limited"))
      (libsource (lib "mylib1") (part "Cap 0603"))
    )
    (comp (ref "C165")
      (value "1u")
      (footprint "CAP 0805")
      (description "Capacitor 0805")
      (fields (field (name "PUBLISHER") "Altium Limited"))
      (libsource (lib "Amin-Library") (part "Cap 0805"))
    )
    (comp (ref "C166")
      (value "1u")
      (footprint "CAP 0805")
      (description "Capacitor 0805")
      (fields (field (name "PUBLISHER") "Altium Limited"))
      (libsource (lib "Amin-Library") (part "Cap 0805"))
    )
    (comp (ref "C167")
      (value "1000u/25v")
      (footprint "CAP DIP 10*13")
      (description "2200ÂµF 50V Aluminum Electrolytic Capacitors Radial, Can 1000 Hrs @ 105Â°C")
      (fields (field (name "MF") "Nichicon") (field (name "MP") "UVZ1H222MHD"))
      (libsource (lib "") (part "capacitor dip 10*13_1"))
    )
    (comp (ref "C168")
      (value "10u")
      (footprint "CAP 0805")
      (description "Capacitor 0805")
      (fields (field (name "PUBLISHER") "Altium Limited"))
      (libsource (lib "Amin-Library") (part "Cap 0805"))
    )
    (comp (ref "C169")
      (value "100n")
      (footprint "cap0603")
      (description "Capacitor 0603")
      (fields (field (name "PUBLISHER") "Altium Limited"))
      (libsource (lib "mylib1") (part "Cap 0603"))
    )
    (comp (ref "C170")
      (value "1000u/25v")
      (footprint "CAP DIP 10*13")
      (description "2200ÂµF 50V Aluminum Electrolytic Capacitors Radial, Can 1000 Hrs @ 105Â°C")
      (fields (field (name "MF") "Nichicon") (field (name "MP") "UVZ1H222MHD"))
      (libsource (lib "") (part "capacitor dip 10*13_1"))
    )
    (comp (ref "C171")
      (value "10u")
      (footprint "CAP 0805")
      (description "Capacitor 0805")
      (fields (field (name "PUBLISHER") "Altium Limited"))
      (libsource (lib "Amin-Library") (part "Cap 0805"))
    )
    (comp (ref "C172")
      (value "100n")
      (footprint "cap0603")
      (description "Capacitor 0603")
      (fields (field (name "PUBLISHER") "Altium Limited"))
      (libsource (lib "mylib1") (part "Cap 0603"))
    )
    (comp (ref "IC2")
      (value "RC4558DR")
      (footprint "RC4558")
      (description "Integrated Circuit SOIC 8")
      (fields (field (name "MOUSER PART NUMBER") "595-RC4558DR"))
      (libsource (lib "STM32F103C8T6") (part "RC4558DR"))
    )
    (comp (ref "J5")
      (value "Con-XH-A")
      (footprint "Con-JST_B2B-XH-A")
      (description "Connector Header Through Hole 2 position 0.098 _2.50mm_")
      (fields (field (name "MP") "B2B-XH-A_LF__SN_") (field (name "MF") "JST Sales"))
      (libsource (lib "Amin-Library") (part "Con-B2B-XH-A"))
    )
    (comp (ref "L1")
      (value "Ferrite-0805")
      (footprint "Ferrite-0805")
      (description "BLM Series 0805 330 Ohm 400 mA 0.58 Ohm DCR Surface Mount Ferrite Bead")
      (fields (field (name "MF") "Murata") (field (name "MP") "BLM18BB331SN1D"))
      (libsource (lib "mylib") (part "Ferrite _0805"))
    )
    (comp (ref "L2")
      (value "10uH, 12*12")
      (footprint "inductor 12*12")
      (description "Inductor round 12*12")
      (fields (field (name "MP") "DR127-330-R") (field (name "MF") "Eaton"))
      (libsource (lib "Amin-Library") (part "INDUCTOR 12*12"))
    )
    (comp (ref "L3")
      (value "10uH, 12*12")
      (footprint "inductor 12*12")
      (description "Inductor round 12*12")
      (fields (field (name "MP") "DR127-330-R") (field (name "MF") "Eaton"))
      (libsource (lib "Amin-Library") (part "INDUCTOR 12*12"))
    )
    (comp (ref "L4")
      (value "10uH, 12*12")
      (footprint "inductor 12*12")
      (description "Inductor round 12*12")
      (fields (field (name "MP") "DR127-330-R") (field (name "MF") "Eaton"))
      (libsource (lib "Amin-Library") (part "INDUCTOR 12*12"))
    )
    (comp (ref "L5")
      (value "10uH, 12*12")
      (footprint "inductor 12*12")
      (description "Inductor round 12*12")
      (fields (field (name "MP") "DR127-330-R") (field (name "MF") "Eaton"))
      (libsource (lib "Amin-Library") (part "INDUCTOR 12*12"))
    )
    (comp (ref "L6")
      (value "10uH, 12*12")
      (footprint "inductor 12*12")
      (description "Inductor round 12*12")
      (fields (field (name "MP") "DR127-330-R") (field (name "MF") "Eaton"))
      (libsource (lib "Amin-Library") (part "INDUCTOR 12*12"))
    )
    (comp (ref "L7")
      (value "10uH, 12*12")
      (footprint "inductor 12*12")
      (description "Inductor round 12*12")
      (fields (field (name "MP") "DR127-330-R") (field (name "MF") "Eaton"))
      (libsource (lib "Amin-Library") (part "INDUCTOR 12*12"))
    )
    (comp (ref "L11")
      (value "10uH, 12*12")
      (footprint "inductor 12*12")
      (description "Inductor round 12*12")
      (fields (field (name "MP") "DR127-330-R") (field (name "MF") "Eaton"))
      (libsource (lib "Amin-Library") (part "INDUCTOR 12*12"))
    )
    (comp (ref "L13")
      (value "10uH, 12*12")
      (footprint "inductor 12*12")
      (description "Inductor round 12*12")
      (fields (field (name "MP") "DR127-330-R") (field (name "MF") "Eaton"))
      (libsource (lib "Amin-Library") (part "INDUCTOR 12*12"))
    )
    (comp (ref "L14")
      (value "10uH, 12*12")
      (footprint "inductor 12*12")
      (description "Inductor round 12*12")
      (fields (field (name "MP") "DR127-330-R") (field (name "MF") "Eaton"))
      (libsource (lib "Amin-Library") (part "INDUCTOR 12*12"))
    )
    (comp (ref "L15")
      (value "10uH, 12*12")
      (footprint "inductor 12*12")
      (description "Inductor round 12*12")
      (fields (field (name "MP") "DR127-330-R") (field (name "MF") "Eaton"))
      (libsource (lib "Amin-Library") (part "INDUCTOR 12*12"))
    )
    (comp (ref "L16")
      (value "10uH, 12*12")
      (footprint "inductor 12*12")
      (description "Inductor round 12*12")
      (fields (field (name "MP") "DR127-330-R") (field (name "MF") "Eaton"))
      (libsource (lib "Amin-Library") (part "INDUCTOR 12*12"))
    )
    (comp (ref "L17")
      (value "10uH, 12*12")
      (footprint "inductor 12*12")
      (description "Inductor round 12*12")
      (fields (field (name "MP") "DR127-330-R") (field (name "MF") "Eaton"))
      (libsource (lib "Amin-Library") (part "INDUCTOR 12*12"))
    )
    (comp (ref "L18")
      (value "10uH, 12*12")
      (footprint "inductor 12*12")
      (description "Inductor round 12*12")
      (fields (field (name "MP") "DR127-330-R") (field (name "MF") "Eaton"))
      (libsource (lib "Amin-Library") (part "INDUCTOR 12*12"))
    )
    (comp (ref "L19")
      (value "10uH, 12*12")
      (footprint "inductor 12*12")
      (description "Inductor round 12*12")
      (fields (field (name "MP") "DR127-330-R") (field (name "MF") "Eaton"))
      (libsource (lib "Amin-Library") (part "INDUCTOR 12*12"))
    )
    (comp (ref "L20")
      (value "10uH, 12*12")
      (footprint "inductor 12*12")
      (description "Inductor round 12*12")
      (fields (field (name "MP") "DR127-330-R") (field (name "MF") "Eaton"))
      (libsource (lib "Amin-Library") (part "INDUCTOR 12*12"))
    )
    (comp (ref "L21")
      (value "10uH, 12*12")
      (footprint "inductor 12*12")
      (description "Inductor round 12*12")
      (fields (field (name "MP") "DR127-330-R") (field (name "MF") "Eaton"))
      (libsource (lib "Amin-Library") (part "INDUCTOR 12*12"))
    )
    (comp (ref "L22")
      (value "10uH, 12*12")
      (footprint "inductor 12*12")
      (description "Inductor round 12*12")
      (fields (field (name "MP") "DR127-330-R") (field (name "MF") "Eaton"))
      (libsource (lib "Amin-Library") (part "INDUCTOR 12*12"))
    )
    (comp (ref "L23")
      (value "10uH, 12*12")
      (footprint "inductor 12*12")
      (description "Inductor round 12*12")
      (fields (field (name "MP") "DR127-330-R") (field (name "MF") "Eaton"))
      (libsource (lib "Amin-Library") (part "INDUCTOR 12*12"))
    )
    (comp (ref "P1")
      (value "Header 2")
      (footprint "CONN-PHOENIX-5.08")
      (description "Phoenix Connector 5.08")
      (fields (field (name "PUBLISHER") "Altium Limited"))
      (libsource (lib "Amin-Library") (part "CONN-Phoenix-5.08"))
    )
    (comp (ref "P3")
      (value "Header 2")
      (footprint "CONN-PHOENIX-5.08")
      (description "Phoenix Connector 5.08")
      (fields (field (name "PUBLISHER") "Altium Limited"))
      (libsource (lib "") (part "CONN-Phoenix-5.08_1"))
    )
    (comp (ref "P5")
      (value "Header 2")
      (footprint "CONN-PHOENIX-3.81")
      (description "Phoenix Connector 3.81")
      (fields (field (name "PUBLISHER") "Altium Limited"))
      (libsource (lib "Amin-Library") (part "CONN-Phoenix-3.81_1"))
    )
    (comp (ref "P7")
      (value "Header 2")
      (footprint "CONN-PHOENIX-5.08")
      (description "Phoenix Connector 5.08")
      (fields (field (name "PUBLISHER") "Altium Limited"))
      (libsource (lib "") (part "CONN-Phoenix-5.08_1"))
    )
    (comp (ref "P8")
      (value "Header 2")
      (footprint "CONN-PHOENIX-5.08")
      (description "Phoenix Connector 5.08")
      (fields (field (name "PUBLISHER") "Altium Limited"))
      (libsource (lib "") (part "CONN-Phoenix-5.08_1"))
    )
    (comp (ref "P9")
      (value "Header 2")
      (footprint "CONN-PHOENIX-5.08")
      (description "Phoenix Connector 5.08")
      (fields (field (name "PUBLISHER") "Altium Limited"))
      (libsource (lib "Amin-Library") (part "CONN-Phoenix-5.08"))
    )
    (comp (ref "P10")
      (value "Header 2")
      (footprint "CONN-PHOENIX-5.08")
      (description "Phoenix Connector 5.08")
      (fields (field (name "PUBLISHER") "Altium Limited"))
      (libsource (lib "Amin-Library") (part "CONN-Phoenix-5.08"))
    )
    (comp (ref "P11")
      (value "Header 2")
      (footprint "CONN-PHOENIX-3.81")
      (description "Phoenix Connector 3.81")
      (fields (field (name "PUBLISHER") "Altium Limited"))
      (libsource (lib "Amin-Library") (part "CONN-Phoenix-3.81_1"))
    )
    (comp (ref "P12")
      (value "Header 2")
      (footprint "CONN-PHOENIX-3.81")
      (description "Phoenix Connector 3.81")
      (fields (field (name "PUBLISHER") "Altium Limited"))
      (libsource (lib "Amin-Library") (part "CONN-Phoenix-3.81_1"))
    )
    (comp (ref "Q7")
      (value "BC817")
      (footprint "BC817")
      (description "NPN General Purpose Amplifier BJT")
      (fields (field (name "PUBLISHER") "Altium Limited"))
      (libsource (lib "Amin-Library") (part "BC817"))
    )
    (comp (ref "R1")
      (value "NC")
      (footprint "RES-0603")
      (description "Resistor 0603")
      (fields (field (name "PUBLISHER") "Altium Limited"))
      (libsource (lib "mylib1") (part "Res 0603"))
    )
    (comp (ref "R2")
      (value "NC")
      (footprint "RES-0603")
      (description "Resistor 0603")
      (fields (field (name "PUBLISHER") "Altium Limited"))
      (libsource (lib "mylib1") (part "Res 0603"))
    )
    (comp (ref "R3")
      (value "NC")
      (footprint "RES-0603")
      (description "Resistor 0603")
      (fields (field (name "PUBLISHER") "Altium Limited"))
      (libsource (lib "mylib1") (part "Res 0603"))
    )
    (comp (ref "R4")
      (value "33K")
      (footprint "RES-0603")
      (description "Resistor 0603")
      (fields (field (name "PUBLISHER") "Altium Limited"))
      (libsource (lib "mylib1") (part "Res 0603"))
    )
    (comp (ref "R5")
      (value "22K")
      (footprint "RES-0603")
      (description "Resistor 0603")
      (fields (field (name "PUBLISHER") "Altium Limited"))
      (libsource (lib "mylib1") (part "Res 0603"))
    )
    (comp (ref "R6")
      (value "27K")
      (footprint "RES-0603")
      (description "Resistor 0603")
      (fields (field (name "PUBLISHER") "Altium Limited"))
      (libsource (lib "mylib1") (part "Res 0603"))
    )
    (comp (ref "R7")
      (value "10k")
      (footprint "RES-0603")
      (description "Resistor 0603")
      (fields (field (name "PUBLISHER") "Altium Limited"))
      (libsource (lib "mylib1") (part "Res 0603"))
    )
    (comp (ref "R8")
      (value "3.3k")
      (footprint "RES-0603")
      (description "Resistor 0603")
      (fields (field (name "PUBLISHER") "Altium Limited"))
      (libsource (lib "mylib1") (part "Res 0603"))
    )
    (comp (ref "R9")
      (value "47k")
      (footprint "RES-0603")
      (description "Resistor 0603")
      (fields (field (name "PUBLISHER") "Altium Limited"))
      (libsource (lib "mylib1") (part "Res 0603"))
    )
    (comp (ref "R10")
      (value "10k")
      (footprint "RES-0603")
      (description "Resistor 0603")
      (fields (field (name "PUBLISHER") "Altium Limited"))
      (libsource (lib "mylib1") (part "Res 0603"))
    )
    (comp (ref "R12")
      (value "10k")
      (footprint "RES-0603")
      (description "Resistor 0603")
      (fields (field (name "PUBLISHER") "Altium Limited"))
      (libsource (lib "mylib1") (part "Res 0603"))
    )
    (comp (ref "R13")
      (value "2.2k")
      (footprint "RES-0603")
      (description "Resistor 0603")
      (fields (field (name "PUBLISHER") "Altium Limited"))
      (libsource (lib "mylib1") (part "Res 0603"))
    )
    (comp (ref "R14")
      (value "2.2k")
      (footprint "RES-0603")
      (description "Resistor 0603")
      (fields (field (name "PUBLISHER") "Altium Limited"))
      (libsource (lib "mylib1") (part "Res 0603"))
    )
    (comp (ref "R16")
      (value "10k")
      (footprint "RES-0603")
      (description "Resistor 0603")
      (fields (field (name "PUBLISHER") "Altium Limited"))
      (libsource (lib "Amin-Library") (part "Res 0603"))
    )
    (comp (ref "R17")
      (value "3.3k")
      (footprint "RES-0603")
      (description "Resistor 0603")
      (fields (field (name "PUBLISHER") "Altium Limited"))
      (libsource (lib "mylib1") (part "Res 0603"))
    )
    (comp (ref "R20")
      (value "1k")
      (footprint "RES-0603")
      (description "Resistor 0603")
      (fields (field (name "PUBLISHER") "Altium Limited"))
      (libsource (lib "Amin-Library") (part "Res 0603"))
    )
    (comp (ref "R21")
      (value "0R")
      (footprint "RES-0603")
      (description "Resistor 0603")
      (fields (field (name "PUBLISHER") "Altium Limited"))
      (libsource (lib "Amin-Library") (part "Res 0603"))
    )
    (comp (ref "R22")
      (value "0R")
      (footprint "RES-0603")
      (description "Resistor 0603")
      (fields (field (name "PUBLISHER") "Altium Limited"))
      (libsource (lib "Amin-Library") (part "Res 0603"))
    )
    (comp (ref "R23")
      (value "33K")
      (footprint "RES-0603")
      (description "Resistor 0603")
      (fields (field (name "PUBLISHER") "Altium Limited"))
      (libsource (lib "mylib1") (part "Res 0603"))
    )
    (comp (ref "R24")
      (value "22K")
      (footprint "RES-0603")
      (description "Resistor 0603")
      (fields (field (name "PUBLISHER") "Altium Limited"))
      (libsource (lib "mylib1") (part "Res 0603"))
    )
    (comp (ref "R29")
      (value "0R")
      (footprint "RES-0603")
      (description "Resistor 0603")
      (fields (field (name "PUBLISHER") "Altium Limited"))
      (libsource (lib "mylib1") (part "Res 0603"))
    )
    (comp (ref "R34")
      (value "0R")
      (footprint "RES-0603")
      (description "Resistor 0603")
      (fields (field (name "PUBLISHER") "Altium Limited"))
      (libsource (lib "mylib1") (part "Res 0603"))
    )
    (comp (ref "R35")
      (value "NC")
      (footprint "RES-0603")
      (description "Resistor 0603")
      (fields (field (name "PUBLISHER") "Altium Limited"))
      (libsource (lib "mylib1") (part "Res 0603"))
    )
    (comp (ref "R36")
      (value "27K")
      (footprint "RES-0603")
      (description "Resistor 0603")
      (fields (field (name "PUBLISHER") "Altium Limited"))
      (libsource (lib "mylib1") (part "Res 0603"))
    )
    (comp (ref "R51")
      (value "1k")
      (footprint "RES-0603")
      (description "Resistor 0603")
      (fields (field (name "PUBLISHER") "Altium Limited"))
      (libsource (lib "Amin-Library") (part "Res 0603"))
    )
    (comp (ref "R53")
      (value "0R")
      (footprint "RES-0603")
      (description "Resistor 0603")
      (fields (field (name "PUBLISHER") "Altium Limited"))
      (libsource (lib "Amin-Library") (part "Res 0603"))
    )
    (comp (ref "R54")
      (value "0R")
      (footprint "RES-0603")
      (description "Resistor 0603")
      (fields (field (name "PUBLISHER") "Altium Limited"))
      (libsource (lib "Amin-Library") (part "Res 0603"))
    )
    (comp (ref "R56")
      (value "NC")
      (footprint "RES-0603")
      (description "Resistor 0603")
      (fields (field (name "PUBLISHER") "Altium Limited"))
      (libsource (lib "mylib1") (part "Res 0603"))
    )
    (comp (ref "R58")
      (value "NC")
      (footprint "RES-0603")
      (description "Resistor 0603")
      (fields (field (name "PUBLISHER") "Altium Limited"))
      (libsource (lib "mylib1") (part "Res 0603"))
    )
    (comp (ref "R59")
      (value "0R")
      (footprint "RES-0603")
      (description "Resistor 0603")
      (fields (field (name "PUBLISHER") "Altium Limited"))
      (libsource (lib "Amin-Library") (part "Res 0603"))
    )
    (comp (ref "R60")
      (value "NC")
      (footprint "RES-0603")
      (description "Resistor 0603")
      (fields (field (name "PUBLISHER") "Altium Limited"))
      (libsource (lib "mylib1") (part "Res 0603"))
    )
    (comp (ref "R61")
      (value "0R")
      (footprint "RES-0603")
      (description "Resistor 0603")
      (fields (field (name "PUBLISHER") "Altium Limited"))
      (libsource (lib "Amin-Library") (part "Res 0603"))
    )
    (comp (ref "R62")
      (value "10k")
      (footprint "RES-0603")
      (description "Resistor 0603")
      (fields (field (name "PUBLISHER") "Altium Limited"))
      (libsource (lib "Amin-Library") (part "Res 0603"))
    )
    (comp (ref "R63")
      (value "4.7k")
      (footprint "RES-0603")
      (description "Resistor 0603")
      (fields (field (name "PUBLISHER") "Altium Limited"))
      (libsource (lib "Amin-Library") (part "Res 0603"))
    )
    (comp (ref "R64")
      (value "NC")
      (footprint "RES-0603")
      (description "Resistor 0603")
      (fields (field (name "PUBLISHER") "Altium Limited"))
      (libsource (lib "mylib1") (part "Res 0603"))
    )
    (comp (ref "R66")
      (value "0R")
      (footprint "RES-0603")
      (description "Resistor 0603")
      (fields (field (name "PUBLISHER") "Altium Limited"))
      (libsource (lib "mylib1") (part "Res 0603"))
    )
    (comp (ref "R67")
      (value "22k")
      (footprint "RES-0603")
      (description "Resistor 0603")
      (fields (field (name "PUBLISHER") "Altium Limited"))
      (libsource (lib "Amin-Library") (part "Res 0603"))
    )
    (comp (ref "R68")
      (value "NTC 10K")
      (footprint "RES-0805")
      (description "resistor 0805")
      (libsource (lib "Amin-Library") (part "Res 0805"))
    )
    (comp (ref "R69")
      (value "0R")
      (footprint "RES-0603")
      (description "Resistor 0603")
      (fields (field (name "PUBLISHER") "Altium Limited"))
      (libsource (lib "mylib1") (part "Res 0603"))
    )
    (comp (ref "R70")
      (value "0R")
      (footprint "RES-0603")
      (description "Resistor 0603")
      (fields (field (name "PUBLISHER") "Altium Limited"))
      (libsource (lib "Amin-Library") (part "Res 0603"))
    )
    (comp (ref "R71")
      (value "0R")
      (footprint "RES-0603")
      (description "Resistor 0603")
      (fields (field (name "PUBLISHER") "Altium Limited"))
      (libsource (lib "Amin-Library") (part "Res 0603"))
    )
    (comp (ref "R72")
      (value "0R")
      (footprint "RES-0603")
      (description "Resistor 0603")
      (fields (field (name "PUBLISHER") "Altium Limited"))
      (libsource (lib "Amin-Library") (part "Res 0603"))
    )
    (comp (ref "R73")
      (value "0R")
      (footprint "RES-0603")
      (description "Resistor 0603")
      (fields (field (name "PUBLISHER") "Altium Limited"))
      (libsource (lib "Amin-Library") (part "Res 0603"))
    )
    (comp (ref "R74")
      (value "0R")
      (footprint "RES-0603")
      (description "Resistor 0603")
      (fields (field (name "PUBLISHER") "Altium Limited"))
      (libsource (lib "Amin-Library") (part "Res 0603"))
    )
    (comp (ref "R75")
      (value "0R")
      (footprint "RES-0603")
      (description "Resistor 0603")
      (fields (field (name "PUBLISHER") "Altium Limited"))
      (libsource (lib "Amin-Library") (part "Res 0603"))
    )
    (comp (ref "R76")
      (value "0R")
      (footprint "RES-0603")
      (description "Resistor 0603")
      (fields (field (name "PUBLISHER") "Altium Limited"))
      (libsource (lib "mylib1") (part "Res 0603"))
    )
    (comp (ref "R77")
      (value "0R")
      (footprint "RES-0603")
      (description "Resistor 0603")
      (fields (field (name "PUBLISHER") "Altium Limited"))
      (libsource (lib "mylib1") (part "Res 0603"))
    )
    (comp (ref "R78")
      (value "0R")
      (footprint "RES-0603")
      (description "Resistor 0603")
      (fields (field (name "PUBLISHER") "Altium Limited"))
      (libsource (lib "Amin-Library") (part "Res 0603"))
    )
    (comp (ref "R79")
      (value "0R")
      (footprint "RES-0603")
      (description "Resistor 0603")
      (fields (field (name "PUBLISHER") "Altium Limited"))
      (libsource (lib "Amin-Library") (part "Res 0603"))
    )
    (comp (ref "R80")
      (value "NC")
      (footprint "RES-0603")
      (description "Resistor 0603")
      (fields (field (name "PUBLISHER") "Altium Limited"))
      (libsource (lib "mylib1") (part "Res 0603"))
    )
    (comp (ref "R81")
      (value "NC")
      (footprint "RES-0603")
      (description "Resistor 0603")
      (fields (field (name "PUBLISHER") "Altium Limited"))
      (libsource (lib "mylib1") (part "Res 0603"))
    )
    (comp (ref "R82")
      (value "NC")
      (footprint "RES-0603")
      (description "Resistor 0603")
      (fields (field (name "PUBLISHER") "Altium Limited"))
      (libsource (lib "mylib1") (part "Res 0603"))
    )
    (comp (ref "R83")
      (value "NC")
      (footprint "RES-0603")
      (description "Resistor 0603")
      (fields (field (name "PUBLISHER") "Altium Limited"))
      (libsource (lib "mylib1") (part "Res 0603"))
    )
    (comp (ref "R84")
      (value "0R")
      (footprint "RES-0603")
      (description "Resistor 0603")
      (fields (field (name "PUBLISHER") "Altium Limited"))
      (libsource (lib "Amin-Library") (part "Res 0603"))
    )
    (comp (ref "R85")
      (value "0R")
      (footprint "RES-0603")
      (description "Resistor 0603")
      (fields (field (name "PUBLISHER") "Altium Limited"))
      (libsource (lib "Amin-Library") (part "Res 0603"))
    )
    (comp (ref "R86")
      (value "0R")
      (footprint "RES-0603")
      (description "Resistor 0603")
      (fields (field (name "PUBLISHER") "Altium Limited"))
      (libsource (lib "Amin-Library") (part "Res 0603"))
    )
    (comp (ref "R87")
      (value "0R")
      (footprint "RES-0603")
      (description "Resistor 0603")
      (fields (field (name "PUBLISHER") "Altium Limited"))
      (libsource (lib "Amin-Library") (part "Res 0603"))
    )
    (comp (ref "U5")
      (value "CS8673E")
      (footprint "CS8673E")
      (description "AB/D 2X40W BTL & 80W PBTL ESOP16")
      (fields
        (field (name "MANUFACTURER_PART_NUMBER") "CS8679E")
        (field (name "MOUSER PART NUMBER") "511-TDA7491HV13TR")
      )
      (libsource (lib "Amin-Library") (part "CS8673E"))
    )
    (comp (ref "U6")
      (value "FAN_12V")
      (footprint "FAN_Connector XH")
      (description "FAN 12V 40*40*10mm . XH Connector")
      (fields (field (name "MANUFACTURER PART") "?") (field (name "CONTRIBUTOR") "novasilisko"))
      (libsource (lib "Amin-Library_S2") (part "FAN_12V"))
    )
    (comp (ref "U7")
      (value "CS8673E")
      (footprint "CS8673E")
      (description "AB/D 2X40W BTL & 80W PBTL ESOP16")
      (fields
        (field (name "MANUFACTURER_PART_NUMBER") "CS8679E")
        (field (name "MOUSER PART NUMBER") "511-TDA7491HV13TR")
      )
      (libsource (lib "Amin-Library") (part "CS8673E"))
    )
    (comp (ref "U9")
      (value "LM321")
      (footprint "LM321")
      (description "Operational Amplifier 5-SOT-23")
      (fields (field (name "MP") "OPA354AIDBVT") (field (name "DIGI-KEY_PART_NUMBER") "296-13033-1-ND"))
      (libsource (lib "Amin-Library") (part "LM321"))
    )
    (comp (ref "U10")
      (value "FAN_Heatsink")
      (footprint "FAN_Heatsink")
      (description "55mm Aluminum Heatsink with Cooling Fan")
      (fields (field (name "MANUFACTURER PART") "?") (field (name "CONTRIBUTOR") "novasilisko"))
      (libsource (lib "Amin-Library") (part "FAN_Heatsink"))
    )
    (comp (ref "U13")
      (value "CS8673E")
      (footprint "CS8673E")
      (description "AB/D 2X40W BTL & 80W PBTL ESOP16")
      (fields
        (field (name "MANUFACTURER_PART_NUMBER") "CS8679E")
        (field (name "MOUSER PART NUMBER") "511-TDA7491HV13TR")
      )
      (libsource (lib "Amin-Library") (part "CS8673E"))
    )
    (comp (ref "U14")
      (value "CS8673E")
      (footprint "CS8673E")
      (description "AB/D 2X40W BTL & 80W PBTL ESOP16")
      (fields
        (field (name "MANUFACTURER_PART_NUMBER") "CS8679E")
        (field (name "MOUSER PART NUMBER") "511-TDA7491HV13TR")
      )
      (libsource (lib "Amin-Library") (part "CS8673E"))
    )
    (comp (ref "U15")
      (value "CS8673E")
      (footprint "CS8673E")
      (description "AB/D 2X40W BTL & 80W PBTL ESOP16")
      (fields
        (field (name "MANUFACTURER_PART_NUMBER") "CS8679E")
        (field (name "MOUSER PART NUMBER") "511-TDA7491HV13TR")
      )
      (libsource (lib "Amin-Library") (part "CS8673E"))
    )
    (comp (ref "U16")
      (value "CS8673E")
      (footprint "CS8673E")
      (description "AB/D 2X40W BTL & 80W PBTL ESOP16")
      (fields
        (field (name "MANUFACTURER_PART_NUMBER") "CS8679E")
        (field (name "MOUSER PART NUMBER") "511-TDA7491HV13TR")
      )
      (libsource (lib "Amin-Library") (part "CS8673E"))
    )
  )
  (nets
    (net (code "1") (name "/BASS+") (class "Default")
      (node (ref "C37") (pin "1") (pinfunction "1_1") (pintype "passive"))
      (node (ref "IC2") (pin "3") (pinfunction "1IN+_3") (pintype "passive"))
      (node (ref "R9") (pin "2") (pinfunction "2_2") (pintype "passive"))
    )
    (net (code "2") (name "/CTRL") (class "Default")
      (node (ref "C10") (pin "2") (pinfunction "2_2") (pintype "passive"))
      (node (ref "R4") (pin "2") (pinfunction "2_2") (pintype "passive"))
      (node (ref "R5") (pin "1") (pinfunction "1_1") (pintype "passive"))
      (node (ref "U13") (pin "2") (pinfunction "CTRL_2") (pintype "passive"))
      (node (ref "U15") (pin "2") (pinfunction "CTRL_2") (pintype "passive"))
    )
    (net (code "3") (name "/CTRL_S") (class "Default")
      (node (ref "C63") (pin "2") (pinfunction "2_2") (pintype "passive"))
      (node (ref "R23") (pin "2") (pinfunction "2_2") (pintype "passive"))
      (node (ref "R24") (pin "1") (pinfunction "1_1") (pintype "passive"))
      (node (ref "U14") (pin "2") (pinfunction "CTRL_2") (pintype "passive"))
      (node (ref "U16") (pin "2") (pinfunction "CTRL_2") (pintype "passive"))
      (node (ref "U5") (pin "2") (pinfunction "CTRL_2") (pintype "passive"))
      (node (ref "U7") (pin "2") (pinfunction "CTRL_2") (pintype "passive"))
    )
    (net (code "4") (name "/EQ") (class "Default")
      (node (ref "C37") (pin "2") (pinfunction "2_2") (pintype "passive"))
      (node (ref "R36") (pin "2") (pinfunction "2_2") (pintype "passive"))
      (node (ref "R6") (pin "1") (pinfunction "1_1") (pintype "passive"))
    )
    (net (code "5") (name "/INA-L+") (class "Default")
      (node (ref "R34") (pin "2") (pinfunction "2_2") (pintype "passive"))
      (node (ref "R6") (pin "2") (pinfunction "2_2") (pintype "passive"))
      (node (ref "R76") (pin "2") (pinfunction "2_2") (pintype "passive"))
      (node (ref "R77") (pin "2") (pinfunction "2_2") (pintype "passive"))
    )
    (net (code "7") (name "/INA-R+") (class "Default")
      (node (ref "R29") (pin "2") (pinfunction "2_2") (pintype "passive"))
      (node (ref "R36") (pin "1") (pinfunction "1_1") (pintype "passive"))
      (node (ref "R66") (pin "2") (pinfunction "2_2") (pintype "passive"))
      (node (ref "R69") (pin "2") (pinfunction "2_2") (pintype "passive"))
    )
    (net (code "9") (name "/INPB") (class "Default")
      (node (ref "C163") (pin "2") (pinfunction "2_2") (pintype "passive"))
      (node (ref "C164") (pin "2") (pinfunction "2_2") (pintype "passive"))
      (node (ref "C39") (pin "2") (pinfunction "2_2") (pintype "passive"))
      (node (ref "C40") (pin "2") (pinfunction "2_2") (pintype "passive"))
      (node (ref "R12") (pin "2") (pinfunction "2_2") (pintype "passive"))
    )
    (net (code "11") (name "/MUTE_P") (class "Default")
      (node (ref "R4") (pin "1") (pinfunction "1_1") (pintype "passive"))
    )
    (net (code "12") (name "/MUTE_S") (class "Default")
      (node (ref "R23") (pin "1") (pinfunction "1_1") (pintype "passive"))
    )
    (net (code "13") (name "12V") (class "Default")
      (node (ref "C7") (pin "2") (pinfunction "2_2") (pintype "passive"))
      (node (ref "C9") (pin "1") (pinfunction "1_1") (pintype "passive"))
      (node (ref "IC2") (pin "8") (pinfunction "VCC+_8") (pintype "passive"))
      (node (ref "R8") (pin "2") (pinfunction "2_2") (pintype "passive"))
    )
    (net (code "14") (name "12V_FAN") (class "Default")
      (node (ref "R16") (pin "2") (pinfunction "2_2") (pintype "passive"))
      (node (ref "R62") (pin "2") (pinfunction "2_2") (pintype "passive"))
      (node (ref "U6") (pin "1") (pinfunction "+_1") (pintype "passive"))
      (node (ref "U9") (pin "5") (pinfunction "V+_5") (pintype "passive"))
    )
    (net (code "15") (name "DS_GND") (class "Default")
      (node (ref "C11") (pin "2") (pinfunction "2_2") (pintype "passive"))
      (node (ref "C118") (pin "2") (pinfunction "2_2") (pintype "passive"))
      (node (ref "C119") (pin "2") (pinfunction "2_2") (pintype "passive"))
      (node (ref "C126") (pin "2") (pinfunction "2_2") (pintype "passive"))
      (node (ref "C127") (pin "2") (pinfunction "2_2") (pintype "passive"))
      (node (ref "C161") (pin "2") (pinfunction "2_2") (pintype "passive"))
      (node (ref "C162") (pin "2") (pinfunction "2_2") (pintype "passive"))
      (node (ref "C40") (pin "1") (pinfunction "1_1") (pintype "passive"))
      (node (ref "C43") (pin "2") (pinfunction "2_2") (pintype "passive"))
      (node (ref "C5") (pin "2") (pinfunction "2_2") (pintype "passive"))
      (node (ref "L1") (pin "2") (pinfunction "2_2") (pintype "passive"))
      (node (ref "R1") (pin "2") (pinfunction "2_2") (pintype "passive"))
      (node (ref "R2") (pin "2") (pinfunction "2_2") (pintype "passive"))
      (node (ref "R3") (pin "1") (pinfunction "1_1") (pintype "passive"))
      (node (ref "R35") (pin "2") (pinfunction "2_2") (pintype "passive"))
      (node (ref "R56") (pin "1") (pinfunction "1_1") (pintype "passive"))
      (node (ref "R58") (pin "1") (pinfunction "1_1") (pintype "passive"))
      (node (ref "R60") (pin "2") (pinfunction "2_2") (pintype "passive"))
      (node (ref "R64") (pin "2") (pinfunction "2_2") (pintype "passive"))
      (node (ref "R80") (pin "2") (pinfunction "2_2") (pintype "passive"))
      (node (ref "R81") (pin "2") (pinfunction "2_2") (pintype "passive"))
      (node (ref "R82") (pin "2") (pinfunction "2_2") (pintype "passive"))
      (node (ref "R83") (pin "2") (pinfunction "2_2") (pintype "passive"))
    )
    (net (code "16") (name "GROUND") (class "Default")
      (node (ref "C10") (pin "1") (pinfunction "1_1") (pintype "passive"))
      (node (ref "C103") (pin "2") (pinfunction "NEG_2") (pintype "passive"))
      (node (ref "C106") (pin "1") (pinfunction "1_1") (pintype "passive"))
      (node (ref "C107") (pin "1") (pinfunction "1_1") (pintype "passive"))
      (node (ref "C116") (pin "2") (pinfunction "2_2") (pintype "passive"))
      (node (ref "C117") (pin "2") (pinfunction "2_2") (pintype "passive"))
      (node (ref "C12") (pin "1") (pinfunction "1_1") (pintype "passive"))
      (node (ref "C120") (pin "1") (pinfunction "1_1") (pintype "passive"))
      (node (ref "C121") (pin "1") (pinfunction "1_1") (pintype "passive"))
      (node (ref "C123") (pin "1") (pinfunction "1_1") (pintype "passive"))
      (node (ref "C125") (pin "1") (pinfunction "1_1") (pintype "passive"))
      (node (ref "C13") (pin "2") (pinfunction "2_2") (pintype "passive"))
      (node (ref "C134") (pin "2") (pinfunction "2_2") (pintype "passive"))
      (node (ref "C135") (pin "2") (pinfunction "2_2") (pintype "passive"))
      (node (ref "C138") (pin "2") (pinfunction "NEG_2") (pintype "passive"))
      (node (ref "C139") (pin "1") (pinfunction "1_1") (pintype "passive"))
      (node (ref "C14") (pin "2") (pinfunction "NEG_2") (pintype "passive"))
      (node (ref "C140") (pin "2") (pinfunction "2_2") (pintype "passive"))
      (node (ref "C141") (pin "2") (pinfunction "NEG_2") (pintype "passive"))
      (node (ref "C143") (pin "1") (pinfunction "1_1") (pintype "passive"))
      (node (ref "C144") (pin "2") (pinfunction "2_2") (pintype "passive"))
      (node (ref "C145") (pin "2") (pinfunction "2_2") (pintype "passive"))
      (node (ref "C146") (pin "1") (pinfunction "1_1") (pintype "passive"))
      (node (ref "C147") (pin "2") (pinfunction "NEG_2") (pintype "passive"))
      (node (ref "C148") (pin "2") (pinfunction "2_2") (pintype "passive"))
      (node (ref "C149") (pin "1") (pinfunction "1_1") (pintype "passive"))
      (node (ref "C15") (pin "1") (pinfunction "1_1") (pintype "passive"))
      (node (ref "C150") (pin "2") (pinfunction "NEG_2") (pintype "passive"))
      (node (ref "C153") (pin "1") (pinfunction "1_1") (pintype "passive"))
      (node (ref "C154") (pin "1") (pinfunction "1_1") (pintype "passive"))
      (node (ref "C155") (pin "1") (pinfunction "1_1") (pintype "passive"))
      (node (ref "C157") (pin "1") (pinfunction "1_1") (pintype "passive"))
      (node (ref "C159") (pin "2") (pinfunction "2_2") (pintype "passive"))
      (node (ref "C16") (pin "1") (pinfunction "1_1") (pintype "passive"))
      (node (ref "C160") (pin "2") (pinfunction "2_2") (pintype "passive"))
      (node (ref "C167") (pin "2") (pinfunction "NEG_2") (pintype "passive"))
      (node (ref "C168") (pin "1") (pinfunction "1_1") (pintype "passive"))
      (node (ref "C169") (pin "2") (pinfunction "2_2") (pintype "passive"))
      (node (ref "C170") (pin "2") (pinfunction "NEG_2") (pintype "passive"))
      (node (ref "C171") (pin "1") (pinfunction "1_1") (pintype "passive"))
      (node (ref "C172") (pin "2") (pinfunction "2_2") (pintype "passive"))
      (node (ref "C18") (pin "2") (pinfunction "2_2") (pintype "passive"))
      (node (ref "C22") (pin "2") (pinfunction "2_2") (pintype "passive"))
      (node (ref "C24") (pin "2") (pinfunction "2_2") (pintype "passive"))
      (node (ref "C25") (pin "2") (pinfunction "NEG_2") (pintype "passive"))
      (node (ref "C26") (pin "1") (pinfunction "1_1") (pintype "passive"))
      (node (ref "C27") (pin "2") (pinfunction "NEG_2") (pintype "passive"))
      (node (ref "C28") (pin "2") (pinfunction "NEG_2") (pintype "passive"))
      (node (ref "C30") (pin "1") (pinfunction "1_1") (pintype "passive"))
      (node (ref "C33") (pin "1") (pinfunction "1_1") (pintype "passive"))
      (node (ref "C35") (pin "1") (pinfunction "1_1") (pintype "passive"))
      (node (ref "C41") (pin "2") (pinfunction "2_2") (pintype "passive"))
      (node (ref "C42") (pin "1") (pinfunction "1_1") (pintype "passive"))
      (node (ref "C45") (pin "1") (pinfunction "1_1") (pintype "passive"))
      (node (ref "C47") (pin "1") (pinfunction "1_1") (pintype "passive"))
      (node (ref "C49") (pin "2") (pinfunction "2_2") (pintype "passive"))
      (node (ref "C53") (pin "2") (pinfunction "NEG_2") (pintype "passive"))
      (node (ref "C55") (pin "1") (pinfunction "1_1") (pintype "passive"))
      (node (ref "C56") (pin "2") (pinfunction "2_2") (pintype "passive"))
      (node (ref "C58") (pin "1") (pinfunction "1_1") (pintype "passive"))
      (node (ref "C6") (pin "2") (pinfunction "2_2") (pintype "passive"))
      (node (ref "C63") (pin "1") (pinfunction "1_1") (pintype "passive"))
      (node (ref "C7") (pin "1") (pinfunction "1_1") (pintype "passive"))
      (node (ref "C84") (pin "2") (pinfunction "2_2") (pintype "passive"))
      (node (ref "C85") (pin "1") (pinfunction "1_1") (pintype "passive"))
      (node (ref "C86") (pin "2") (pinfunction "NEG_2") (pintype "passive"))
      (node (ref "C87") (pin "2") (pinfunction "2_2") (pintype "passive"))
      (node (ref "C88") (pin "1") (pinfunction "1_1") (pintype "passive"))
      (node (ref "C9") (pin "2") (pinfunction "2_2") (pintype "passive"))
      (node (ref "IC2") (pin "4") (pinfunction "VCC-_4") (pintype "passive"))
      (node (ref "J5") (pin "2") (pinfunction "2_2") (pintype "passive"))
      (node (ref "L1") (pin "1") (pinfunction "1_1") (pintype "passive"))
      (node (ref "Q7") (pin "2") (pinfunction "E_2") (pintype "passive"))
      (node (ref "R13") (pin "1") (pinfunction "1_1") (pintype "passive"))
      (node (ref "R24") (pin "2") (pinfunction "2_2") (pintype "passive"))
      (node (ref "R5") (pin "2") (pinfunction "2_2") (pintype "passive"))
      (node (ref "R51") (pin "1") (pinfunction "1_1") (pintype "passive"))
      (node (ref "R63") (pin "2") (pinfunction "2_2") (pintype "passive"))
      (node (ref "R68") (pin "1") (pinfunction "1_1") (pintype "passive"))
      (node (ref "U13") (pin "17") (pinfunction "PGND_17") (pintype "passive"))
      (node (ref "U14") (pin "17") (pinfunction "PGND_17") (pintype "passive"))
      (node (ref "U15") (pin "17") (pinfunction "PGND_17") (pintype "passive"))
      (node (ref "U15") (pin "3") (pinfunction "INPL_3") (pintype "passive"))
      (node (ref "U15") (pin "4") (pinfunction "INNL_4") (pintype "passive"))
      (node (ref "U16") (pin "17") (pinfunction "PGND_17") (pintype "passive"))
      (node (ref "U16") (pin "3") (pinfunction "INPL_3") (pintype "passive"))
      (node (ref "U16") (pin "4") (pinfunction "INNL_4") (pintype "passive"))
      (node (ref "U5") (pin "17") (pinfunction "PGND_17") (pintype "passive"))
      (node (ref "U7") (pin "17") (pinfunction "PGND_17") (pintype "passive"))
      (node (ref "U7") (pin "3") (pinfunction "INPL_3") (pintype "passive"))
      (node (ref "U7") (pin "4") (pinfunction "INNL_4") (pintype "passive"))
      (node (ref "U9") (pin "2") (pinfunction "V-_2") (pintype "passive"))
    )
    (net (code "17") (name "Net-(C2-Pad1)") (class "Default")
      (node (ref "C2") (pin "1") (pinfunction "1_1") (pintype "passive"))
      (node (ref "C3") (pin "1") (pinfunction "1_1") (pintype "passive"))
      (node (ref "R1") (pin "1") (pinfunction "1_1") (pintype "passive"))
    )
    (net (code "18") (name "Net-(C2-Pad2)") (class "Default")
      (node (ref "C2") (pin "2") (pinfunction "2_2") (pintype "passive"))
      (node (ref "R53") (pin "1") (pinfunction "1_1") (pintype "passive"))
    )
    (net (code "19") (name "Net-(C3-Pad2)") (class "Default")
      (node (ref "C3") (pin "2") (pinfunction "2_2") (pintype "passive"))
      (node (ref "R34") (pin "1") (pinfunction "1_1") (pintype "passive"))
      (node (ref "R35") (pin "1") (pinfunction "1_1") (pintype "passive"))
    )
    (net (code "20") (name "Net-(C4-Pad1)") (class "Default")
      (node (ref "C4") (pin "1") (pinfunction "1_1") (pintype "passive"))
      (node (ref "C8") (pin "2") (pinfunction "2_2") (pintype "passive"))
      (node (ref "R2") (pin "1") (pinfunction "1_1") (pintype "passive"))
    )
    (net (code "21") (name "Net-(C4-Pad2)") (class "Default")
      (node (ref "C4") (pin "2") (pinfunction "2_2") (pintype "passive"))
      (node (ref "R29") (pin "1") (pinfunction "1_1") (pintype "passive"))
      (node (ref "R3") (pin "2") (pinfunction "2_2") (pintype "passive"))
    )
    (net (code "22") (name "Net-(C5-Pad1)") (class "Default")
      (node (ref "C5") (pin "1") (pinfunction "1_1") (pintype "passive"))
      (node (ref "R54") (pin "1") (pinfunction "1_1") (pintype "passive"))
    )
    (net (code "23") (name "Net-(C8-Pad1)") (class "Default")
      (node (ref "C8") (pin "1") (pinfunction "1_1") (pintype "passive"))
      (node (ref "R59") (pin "1") (pinfunction "1_1") (pintype "passive"))
    )
    (net (code "24") (name "Net-(C11-Pad1)") (class "Default")
      (node (ref "C11") (pin "1") (pinfunction "1_1") (pintype "passive"))
      (node (ref "R61") (pin "1") (pinfunction "1_1") (pintype "passive"))
    )
    (net (code "25") (name "Net-(C15-Pad2)") (class "Default")
      (node (ref "C15") (pin "2") (pinfunction "2_2") (pintype "passive"))
      (node (ref "C46") (pin "2") (pinfunction "2_2") (pintype "passive"))
      (node (ref "L2") (pin "1") (pinfunction "1_1") (pintype "passive"))
      (node (ref "P1") (pin "2") (pinfunction "2_2") (pintype "passive"))
    )
    (net (code "26") (name "Net-(C18-Pad1)") (class "Default")
      (node (ref "C18") (pin "1") (pinfunction "1_1") (pintype "passive"))
      (node (ref "C46") (pin "1") (pinfunction "1_1") (pintype "passive"))
      (node (ref "L3") (pin "1") (pinfunction "1_1") (pintype "passive"))
      (node (ref "P1") (pin "1") (pinfunction "1_1") (pintype "passive"))
    )
    (net (code "27") (name "Net-(C32-Pad2)") (class "Default")
      (node (ref "C32") (pin "2") (pinfunction "2_2") (pintype "passive"))
      (node (ref "R12") (pin "1") (pinfunction "1_1") (pintype "passive"))
    )
    (net (code "28") (name "Net-(C33-Pad2)") (class "Default")
      (node (ref "C33") (pin "2") (pinfunction "2_2") (pintype "passive"))
      (node (ref "R13") (pin "2") (pinfunction "2_2") (pintype "passive"))
      (node (ref "R8") (pin "1") (pinfunction "1_1") (pintype "passive"))
      (node (ref "R9") (pin "1") (pinfunction "1_1") (pintype "passive"))
    )
    (net (code "29") (name "Net-(C34-Pad1)") (class "Default")
      (node (ref "C34") (pin "1") (pinfunction "1_1") (pintype "passive"))
      (node (ref "C41") (pin "1") (pinfunction "1_1") (pintype "passive"))
      (node (ref "L7") (pin "1") (pinfunction "1_1") (pintype "passive"))
      (node (ref "P3") (pin "2") (pinfunction "2_2") (pintype "passive"))
    )
    (net (code "30") (name "Net-(C34-Pad2)") (class "Default")
      (node (ref "C34") (pin "2") (pinfunction "2_2") (pintype "passive"))
      (node (ref "C35") (pin "2") (pinfunction "2_2") (pintype "passive"))
      (node (ref "L6") (pin "1") (pinfunction "1_1") (pintype "passive"))
      (node (ref "P3") (pin "1") (pinfunction "1_1") (pintype "passive"))
    )
    (net (code "31") (name "Net-(C36-Pad2)") (class "Default")
      (node (ref "C36") (pin "2") (pinfunction "2_2") (pintype "passive"))
      (node (ref "R10") (pin "1") (pinfunction "1_1") (pintype "passive"))
      (node (ref "R7") (pin "1") (pinfunction "1_1") (pintype "passive"))
    )
    (net (code "32") (name "Net-(C39-Pad1)") (class "Default")
      (node (ref "C39") (pin "1") (pinfunction "1_1") (pintype "passive"))
      (node (ref "R21") (pin "1") (pinfunction "1_1") (pintype "passive"))
    )
    (net (code "33") (name "Net-(C42-Pad2)") (class "Default")
      (node (ref "C42") (pin "2") (pinfunction "2_2") (pintype "passive"))
      (node (ref "R14") (pin "1") (pinfunction "1_1") (pintype "passive"))
    )
    (net (code "34") (name "Net-(C43-Pad1)") (class "Default")
      (node (ref "C43") (pin "1") (pinfunction "1_1") (pintype "passive"))
      (node (ref "R22") (pin "1") (pinfunction "1_1") (pintype "passive"))
    )
    (net (code "35") (name "Net-(C47-Pad2)") (class "Default")
      (node (ref "C47") (pin "2") (pinfunction "2_2") (pintype "passive"))
      (node (ref "C48") (pin "2") (pinfunction "2_2") (pintype "passive"))
      (node (ref "L4") (pin "1") (pinfunction "1_1") (pintype "passive"))
      (node (ref "P5") (pin "2") (pinfunction "2_2") (pintype "passive"))
    )
    (net (code "36") (name "Net-(C48-Pad1)") (class "Default")
      (node (ref "C48") (pin "1") (pinfunction "1_1") (pintype "passive"))
      (node (ref "C49") (pin "1") (pinfunction "1_1") (pintype "passive"))
      (node (ref "L5") (pin "1") (pinfunction "1_1") (pintype "passive"))
      (node (ref "P5") (pin "1") (pinfunction "1_1") (pintype "passive"))
    )
    (net (code "37") (name "Net-(C106-Pad2)") (class "Default")
      (node (ref "C106") (pin "2") (pinfunction "2_2") (pintype "passive"))
      (node (ref "C110") (pin "2") (pinfunction "2_2") (pintype "passive"))
      (node (ref "L11") (pin "1") (pinfunction "1_1") (pintype "passive"))
      (node (ref "P7") (pin "1") (pinfunction "1_1") (pintype "passive"))
    )
    (net (code "38") (name "Net-(C107-Pad2)") (class "Default")
      (node (ref "C107") (pin "2") (pinfunction "2_2") (pintype "passive"))
      (node (ref "C113") (pin "2") (pinfunction "2_2") (pintype "passive"))
      (node (ref "L13") (pin "1") (pinfunction "1_1") (pintype "passive"))
      (node (ref "P8") (pin "1") (pinfunction "1_1") (pintype "passive"))
    )
    (net (code "39") (name "Net-(C108-Pad1)") (class "Default")
      (node (ref "C108") (pin "1") (pinfunction "1_1") (pintype "passive"))
      (node (ref "C114") (pin "2") (pinfunction "2_2") (pintype "passive"))
      (node (ref "R60") (pin "1") (pinfunction "1_1") (pintype "passive"))
    )
    (net (code "40") (name "Net-(C108-Pad2)") (class "Default")
      (node (ref "C108") (pin "2") (pinfunction "2_2") (pintype "passive"))
      (node (ref "R56") (pin "2") (pinfunction "2_2") (pintype "passive"))
      (node (ref "R66") (pin "1") (pinfunction "1_1") (pintype "passive"))
    )
    (net (code "41") (name "Net-(C110-Pad1)") (class "Default")
      (node (ref "C110") (pin "1") (pinfunction "1_1") (pintype "passive"))
      (node (ref "C116") (pin "1") (pinfunction "1_1") (pintype "passive"))
      (node (ref "L14") (pin "1") (pinfunction "1_1") (pintype "passive"))
      (node (ref "P7") (pin "2") (pinfunction "2_2") (pintype "passive"))
    )
    (net (code "42") (name "Net-(C111-Pad1)") (class "Default")
      (node (ref "C111") (pin "1") (pinfunction "1_1") (pintype "passive"))
      (node (ref "C115") (pin "2") (pinfunction "2_2") (pintype "passive"))
      (node (ref "R64") (pin "1") (pinfunction "1_1") (pintype "passive"))
    )
    (net (code "43") (name "Net-(C111-Pad2)") (class "Default")
      (node (ref "C111") (pin "2") (pinfunction "2_2") (pintype "passive"))
      (node (ref "R58") (pin "2") (pinfunction "2_2") (pintype "passive"))
      (node (ref "R69") (pin "1") (pinfunction "1_1") (pintype "passive"))
    )
    (net (code "44") (name "Net-(C113-Pad1)") (class "Default")
      (node (ref "C113") (pin "1") (pinfunction "1_1") (pintype "passive"))
      (node (ref "C117") (pin "1") (pinfunction "1_1") (pintype "passive"))
      (node (ref "L15") (pin "1") (pinfunction "1_1") (pintype "passive"))
      (node (ref "P8") (pin "2") (pinfunction "2_2") (pintype "passive"))
    )
    (net (code "45") (name "Net-(C114-Pad1)") (class "Default")
      (node (ref "C114") (pin "1") (pinfunction "1_1") (pintype "passive"))
      (node (ref "R70") (pin "1") (pinfunction "1_1") (pintype "passive"))
    )
    (net (code "46") (name "Net-(C115-Pad1)") (class "Default")
      (node (ref "C115") (pin "1") (pinfunction "1_1") (pintype "passive"))
      (node (ref "R71") (pin "1") (pinfunction "1_1") (pintype "passive"))
    )
    (net (code "47") (name "Net-(C118-Pad1)") (class "Default")
      (node (ref "C118") (pin "1") (pinfunction "1_1") (pintype "passive"))
      (node (ref "R72") (pin "1") (pinfunction "1_1") (pintype "passive"))
    )
    (net (code "48") (name "Net-(C119-Pad1)") (class "Default")
      (node (ref "C119") (pin "1") (pinfunction "1_1") (pintype "passive"))
      (node (ref "R73") (pin "1") (pinfunction "1_1") (pintype "passive"))
    )
    (net (code "49") (name "Net-(C123-Pad2)") (class "Default")
      (node (ref "C123") (pin "2") (pinfunction "2_2") (pintype "passive"))
      (node (ref "C129") (pin "2") (pinfunction "2_2") (pintype "passive"))
      (node (ref "L16") (pin "1") (pinfunction "1_1") (pintype "passive"))
      (node (ref "P9") (pin "2") (pinfunction "2_2") (pintype "passive"))
    )
    (net (code "50") (name "Net-(C125-Pad2)") (class "Default")
      (node (ref "C125") (pin "2") (pinfunction "2_2") (pintype "passive"))
      (node (ref "C131") (pin "2") (pinfunction "2_2") (pintype "passive"))
      (node (ref "L17") (pin "1") (pinfunction "1_1") (pintype "passive"))
      (node (ref "P10") (pin "2") (pinfunction "2_2") (pintype "passive"))
    )
    (net (code "51") (name "Net-(C126-Pad1)") (class "Default")
      (node (ref "C126") (pin "1") (pinfunction "1_1") (pintype "passive"))
      (node (ref "R74") (pin "1") (pinfunction "1_1") (pintype "passive"))
    )
    (net (code "52") (name "Net-(C127-Pad1)") (class "Default")
      (node (ref "C127") (pin "1") (pinfunction "1_1") (pintype "passive"))
      (node (ref "R75") (pin "1") (pinfunction "1_1") (pintype "passive"))
    )
    (net (code "53") (name "Net-(C128-Pad1)") (class "Default")
      (node (ref "C128") (pin "1") (pinfunction "1_1") (pintype "passive"))
      (node (ref "C132") (pin "1") (pinfunction "1_1") (pintype "passive"))
      (node (ref "R81") (pin "1") (pinfunction "1_1") (pintype "passive"))
    )
    (net (code "54") (name "Net-(C128-Pad2)") (class "Default")
      (node (ref "C128") (pin "2") (pinfunction "2_2") (pintype "passive"))
      (node (ref "R76") (pin "1") (pinfunction "1_1") (pintype "passive"))
      (node (ref "R80") (pin "1") (pinfunction "1_1") (pintype "passive"))
    )
    (net (code "55") (name "Net-(C129-Pad1)") (class "Default")
      (node (ref "C129") (pin "1") (pinfunction "1_1") (pintype "passive"))
      (node (ref "C134") (pin "1") (pinfunction "1_1") (pintype "passive"))
      (node (ref "L18") (pin "1") (pinfunction "1_1") (pintype "passive"))
      (node (ref "P9") (pin "1") (pinfunction "1_1") (pintype "passive"))
    )
    (net (code "56") (name "Net-(C130-Pad1)") (class "Default")
      (node (ref "C130") (pin "1") (pinfunction "1_1") (pintype "passive"))
      (node (ref "C133") (pin "1") (pinfunction "1_1") (pintype "passive"))
      (node (ref "R83") (pin "1") (pinfunction "1_1") (pintype "passive"))
    )
    (net (code "57") (name "Net-(C130-Pad2)") (class "Default")
      (node (ref "C130") (pin "2") (pinfunction "2_2") (pintype "passive"))
      (node (ref "R77") (pin "1") (pinfunction "1_1") (pintype "passive"))
      (node (ref "R82") (pin "1") (pinfunction "1_1") (pintype "passive"))
    )
    (net (code "58") (name "Net-(C131-Pad1)") (class "Default")
      (node (ref "C131") (pin "1") (pinfunction "1_1") (pintype "passive"))
      (node (ref "C135") (pin "1") (pinfunction "1_1") (pintype "passive"))
      (node (ref "L19") (pin "1") (pinfunction "1_1") (pintype "passive"))
      (node (ref "P10") (pin "1") (pinfunction "1_1") (pintype "passive"))
    )
    (net (code "59") (name "Net-(C132-Pad2)") (class "Default")
      (node (ref "C132") (pin "2") (pinfunction "2_2") (pintype "passive"))
      (node (ref "R78") (pin "1") (pinfunction "1_1") (pintype "passive"))
    )
    (net (code "60") (name "Net-(C133-Pad2)") (class "Default")
      (node (ref "C133") (pin "2") (pinfunction "2_2") (pintype "passive"))
      (node (ref "R79") (pin "1") (pinfunction "1_1") (pintype "passive"))
    )
    (net (code "61") (name "Net-(C153-Pad2)") (class "Default")
      (node (ref "C153") (pin "2") (pinfunction "2_2") (pintype "passive"))
      (node (ref "C156") (pin "2") (pinfunction "2_2") (pintype "passive"))
      (node (ref "L20") (pin "1") (pinfunction "1_1") (pintype "passive"))
      (node (ref "P11") (pin "2") (pinfunction "2_2") (pintype "passive"))
    )
    (net (code "62") (name "Net-(C154-Pad2)") (class "Default")
      (node (ref "C154") (pin "2") (pinfunction "2_2") (pintype "passive"))
      (node (ref "C158") (pin "2") (pinfunction "2_2") (pintype "passive"))
      (node (ref "L21") (pin "1") (pinfunction "1_1") (pintype "passive"))
      (node (ref "P12") (pin "2") (pinfunction "2_2") (pintype "passive"))
    )
    (net (code "63") (name "Net-(C156-Pad1)") (class "Default")
      (node (ref "C156") (pin "1") (pinfunction "1_1") (pintype "passive"))
      (node (ref "C159") (pin "1") (pinfunction "1_1") (pintype "passive"))
      (node (ref "L22") (pin "1") (pinfunction "1_1") (pintype "passive"))
      (node (ref "P11") (pin "1") (pinfunction "1_1") (pintype "passive"))
    )
    (net (code "64") (name "Net-(C158-Pad1)") (class "Default")
      (node (ref "C158") (pin "1") (pinfunction "1_1") (pintype "passive"))
      (node (ref "C160") (pin "1") (pinfunction "1_1") (pintype "passive"))
      (node (ref "L23") (pin "1") (pinfunction "1_1") (pintype "passive"))
      (node (ref "P12") (pin "1") (pinfunction "1_1") (pintype "passive"))
    )
    (net (code "65") (name "Net-(C161-Pad1)") (class "Default")
      (node (ref "C161") (pin "1") (pinfunction "1_1") (pintype "passive"))
      (node (ref "R84") (pin "1") (pinfunction "1_1") (pintype "passive"))
    )
    (net (code "66") (name "Net-(C162-Pad1)") (class "Default")
      (node (ref "C162") (pin "1") (pinfunction "1_1") (pintype "passive"))
      (node (ref "R85") (pin "1") (pinfunction "1_1") (pintype "passive"))
    )
    (net (code "67") (name "Net-(C163-Pad1)") (class "Default")
      (node (ref "C163") (pin "1") (pinfunction "1_1") (pintype "passive"))
      (node (ref "R86") (pin "1") (pinfunction "1_1") (pintype "passive"))
    )
    (net (code "68") (name "Net-(C164-Pad1)") (class "Default")
      (node (ref "C164") (pin "1") (pinfunction "1_1") (pintype "passive"))
      (node (ref "R87") (pin "1") (pinfunction "1_1") (pintype "passive"))
    )
    (net (code "69") (name "Net-(IC2A-1IN-)") (class "Default")
      (node (ref "IC2") (pin "2") (pinfunction "1IN-_2") (pintype "passive"))
      (node (ref "R14") (pin "2") (pinfunction "2_2") (pintype "passive"))
      (node (ref "R17") (pin "2") (pinfunction "2_2") (pintype "passive"))
    )
    (net (code "70") (name "Net-(IC2A-1OUT)") (class "Default")
      (node (ref "IC2") (pin "1") (pinfunction "1OUT_1") (pintype "passive"))
      (node (ref "R10") (pin "2") (pinfunction "2_2") (pintype "passive"))
      (node (ref "R17") (pin "1") (pinfunction "1_1") (pintype "passive"))
    )
    (net (code "71") (name "Net-(IC2B-2IN+)") (class "Default")
      (node (ref "C30") (pin "2") (pinfunction "2_2") (pintype "passive"))
      (node (ref "IC2") (pin "5") (pinfunction "2IN+_5") (pintype "passive"))
      (node (ref "R7") (pin "2") (pinfunction "2_2") (pintype "passive"))
    )
    (net (code "72") (name "Net-(IC2B-2IN-)") (class "Default")
      (node (ref "C32") (pin "1") (pinfunction "1_1") (pintype "passive"))
      (node (ref "C36") (pin "1") (pinfunction "1_1") (pintype "passive"))
      (node (ref "IC2") (pin "6") (pinfunction "2IN-_6") (pintype "passive"))
      (node (ref "IC2") (pin "7") (pinfunction "2OUT_7") (pintype "passive"))
    )
    (net (code "73") (name "Net-(Q7-B)") (class "Default")
      (node (ref "Q7") (pin "1") (pinfunction "B_1") (pintype "passive"))
      (node (ref "R20") (pin "2") (pinfunction "2_2") (pintype "passive"))
      (node (ref "R63") (pin "1") (pinfunction "1_1") (pintype "passive"))
    )
    (net (code "74") (name "Net-(Q7-C)") (class "Default")
      (node (ref "Q7") (pin "3") (pinfunction "C_3") (pintype "passive"))
      (node (ref "U6") (pin "2") (pinfunction "-_2") (pintype "passive"))
    )
    (net (code "75") (name "Net-(U5-BSMNR)") (class "Default")
      (node (ref "C21") (pin "2") (pinfunction "2_2") (pintype "passive"))
      (node (ref "U5") (pin "11") (pinfunction "BSMNR_11") (pintype "passive"))
    )
    (net (code "76") (name "Net-(U5-BSNL)") (class "Default")
      (node (ref "C20") (pin "2") (pinfunction "2_2") (pintype "passive"))
      (node (ref "U5") (pin "14") (pinfunction "BSNL_14") (pintype "passive"))
    )
    (net (code "77") (name "Net-(U5-BSPL)") (class "Default")
      (node (ref "C17") (pin "2") (pinfunction "2_2") (pintype "passive"))
      (node (ref "U5") (pin "16") (pinfunction "BSPL_16") (pintype "passive"))
    )
    (net (code "78") (name "Net-(U5-GVDD)") (class "Default")
      (node (ref "C58") (pin "2") (pinfunction "2_2") (pintype "passive"))
      (node (ref "U5") (pin "5") (pinfunction "GVDD_5") (pintype "passive"))
    )
    (net (code "79") (name "Net-(U5-INNL)") (class "Default")
      (node (ref "R61") (pin "2") (pinfunction "2_2") (pintype "passive"))
      (node (ref "U5") (pin "4") (pinfunction "INNL_4") (pintype "passive"))
    )
    (net (code "80") (name "Net-(U5-INNR)") (class "Default")
      (node (ref "R54") (pin "2") (pinfunction "2_2") (pintype "passive"))
      (node (ref "U5") (pin "6") (pinfunction "INNR_6") (pintype "passive"))
    )
    (net (code "81") (name "Net-(U5-INPL)") (class "Default")
      (node (ref "R59") (pin "2") (pinfunction "2_2") (pintype "passive"))
      (node (ref "U5") (pin "3") (pinfunction "INPL_3") (pintype "passive"))
    )
    (net (code "82") (name "Net-(U5-INPR)") (class "Default")
      (node (ref "R53") (pin "2") (pinfunction "2_2") (pintype "passive"))
      (node (ref "U5") (pin "7") (pinfunction "INPR_7") (pintype "passive"))
    )
    (net (code "83") (name "Net-(U5-OUTNL)") (class "Default")
      (node (ref "C20") (pin "1") (pinfunction "1_1") (pintype "passive"))
      (node (ref "L7") (pin "2") (pinfunction "2_2") (pintype "passive"))
      (node (ref "U5") (pin "13") (pinfunction "OUTNL_13") (pintype "passive"))
    )
    (net (code "84") (name "Net-(U5-OUTNR)") (class "Default")
      (node (ref "C21") (pin "1") (pinfunction "1_1") (pintype "passive"))
      (node (ref "L2") (pin "2") (pinfunction "2_2") (pintype "passive"))
      (node (ref "U5") (pin "12") (pinfunction "OUTNR_12") (pintype "passive"))
    )
    (net (code "85") (name "Net-(U5-OUTPL)") (class "Default")
      (node (ref "C17") (pin "1") (pinfunction "1_1") (pintype "passive"))
      (node (ref "L6") (pin "2") (pinfunction "2_2") (pintype "passive"))
      (node (ref "U5") (pin "15") (pinfunction "OUTPL_15") (pintype "passive"))
    )
    (net (code "86") (name "Net-(U5-OUTPR)") (class "Default")
      (node (ref "C31") (pin "1") (pinfunction "1_1") (pintype "passive"))
      (node (ref "L3") (pin "2") (pinfunction "2_2") (pintype "passive"))
      (node (ref "U5") (pin "10") (pinfunction "OUTPR_10") (pintype "passive"))
    )
    (net (code "87") (name "Net-(U5-PSPR)") (class "Default")
      (node (ref "C31") (pin "2") (pinfunction "2_2") (pintype "passive"))
      (node (ref "U5") (pin "9") (pinfunction "PSPR_9") (pintype "passive"))
    )
    (net (code "88") (name "Net-(U7-BSMNR)") (class "Default")
      (node (ref "C50") (pin "2") (pinfunction "2_2") (pintype "passive"))
      (node (ref "U7") (pin "11") (pinfunction "BSMNR_11") (pintype "passive"))
      (node (ref "U7") (pin "9") (pinfunction "PSPR_9") (pintype "passive"))
    )
    (net (code "89") (name "Net-(U7-BSNL)") (class "Default")
      (node (ref "C38") (pin "2") (pinfunction "2_2") (pintype "passive"))
      (node (ref "U7") (pin "14") (pinfunction "BSNL_14") (pintype "passive"))
      (node (ref "U7") (pin "16") (pinfunction "BSPL_16") (pintype "passive"))
    )
    (net (code "90") (name "Net-(U7-GVDD)") (class "Default")
      (node (ref "C45") (pin "2") (pinfunction "2_2") (pintype "passive"))
      (node (ref "U7") (pin "5") (pinfunction "GVDD_5") (pintype "passive"))
    )
    (net (code "91") (name "Net-(U7-INNR)") (class "Default")
      (node (ref "R22") (pin "2") (pinfunction "2_2") (pintype "passive"))
      (node (ref "U7") (pin "6") (pinfunction "INNR_6") (pintype "passive"))
    )
    (net (code "92") (name "Net-(U7-INPR)") (class "Default")
      (node (ref "R21") (pin "2") (pinfunction "2_2") (pintype "passive"))
      (node (ref "U7") (pin "7") (pinfunction "INPR_7") (pintype "passive"))
    )
    (net (code "93") (name "Net-(U7-OUTNL)") (class "Default")
      (node (ref "C38") (pin "1") (pinfunction "1_1") (pintype "passive"))
      (node (ref "L4") (pin "2") (pinfunction "2_2") (pintype "passive"))
      (node (ref "U7") (pin "13") (pinfunction "OUTNL_13") (pintype "passive"))
      (node (ref "U7") (pin "15") (pinfunction "OUTPL_15") (pintype "passive"))
    )
    (net (code "94") (name "Net-(U7-OUTNR)") (class "Default")
      (node (ref "C50") (pin "1") (pinfunction "1_1") (pintype "passive"))
      (node (ref "L5") (pin "2") (pinfunction "2_2") (pintype "passive"))
      (node (ref "U7") (pin "10") (pinfunction "OUTPR_10") (pintype "passive"))
      (node (ref "U7") (pin "12") (pinfunction "OUTNR_12") (pintype "passive"))
    )
    (net (code "95") (name "Net-(U9-1IN+)") (class "Default")
      (node (ref "R16") (pin "1") (pinfunction "1_1") (pintype "passive"))
      (node (ref "R51") (pin "2") (pinfunction "2_2") (pintype "passive"))
      (node (ref "R67") (pin "1") (pinfunction "1_1") (pintype "passive"))
      (node (ref "U9") (pin "1") (pinfunction "1IN+_1") (pintype "passive"))
    )
    (net (code "96") (name "Net-(U9-1IN-)") (class "Default")
      (node (ref "R62") (pin "1") (pinfunction "1_1") (pintype "passive"))
      (node (ref "R68") (pin "2") (pinfunction "2_2") (pintype "passive"))
      (node (ref "U9") (pin "3") (pinfunction "1IN-_3") (pintype "passive"))
    )
    (net (code "97") (name "Net-(U9-1OUT)") (class "Default")
      (node (ref "R20") (pin "1") (pinfunction "1_1") (pintype "passive"))
      (node (ref "R67") (pin "2") (pinfunction "2_2") (pintype "passive"))
      (node (ref "U9") (pin "4") (pinfunction "1OUT_4") (pintype "passive"))
    )
    (net (code "98") (name "Net-(U13-BSMNR)") (class "Default")
      (node (ref "C122") (pin "2") (pinfunction "2_2") (pintype "passive"))
      (node (ref "U13") (pin "11") (pinfunction "BSMNR_11") (pintype "passive"))
    )
    (net (code "99") (name "Net-(U13-BSNL)") (class "Default")
      (node (ref "C109") (pin "2") (pinfunction "2_2") (pintype "passive"))
      (node (ref "U13") (pin "14") (pinfunction "BSNL_14") (pintype "passive"))
    )
    (net (code "100") (name "Net-(U13-BSPL)") (class "Default")
      (node (ref "C104") (pin "2") (pinfunction "2_2") (pintype "passive"))
      (node (ref "U13") (pin "16") (pinfunction "BSPL_16") (pintype "passive"))
    )
    (net (code "101") (name "Net-(U13-GVDD)") (class "Default")
      (node (ref "C120") (pin "2") (pinfunction "2_2") (pintype "passive"))
      (node (ref "U13") (pin "5") (pinfunction "GVDD_5") (pintype "passive"))
    )
    (net (code "102") (name "Net-(U13-INNL)") (class "Default")
      (node (ref "R72") (pin "2") (pinfunction "2_2") (pintype "passive"))
      (node (ref "U13") (pin "4") (pinfunction "INNL_4") (pintype "passive"))
    )
    (net (code "103") (name "Net-(U13-INNR)") (class "Default")
      (node (ref "R74") (pin "2") (pinfunction "2_2") (pintype "passive"))
      (node (ref "U13") (pin "6") (pinfunction "INNR_6") (pintype "passive"))
    )
    (net (code "104") (name "Net-(U13-INPL)") (class "Default")
      (node (ref "R70") (pin "2") (pinfunction "2_2") (pintype "passive"))
      (node (ref "U13") (pin "3") (pinfunction "INPL_3") (pintype "passive"))
    )
    (net (code "105") (name "Net-(U13-INPR)") (class "Default")
      (node (ref "R78") (pin "2") (pinfunction "2_2") (pintype "passive"))
      (node (ref "U13") (pin "7") (pinfunction "INPR_7") (pintype "passive"))
    )
    (net (code "106") (name "Net-(U13-OUTNL)") (class "Default")
      (node (ref "C109") (pin "1") (pinfunction "1_1") (pintype "passive"))
      (node (ref "L14") (pin "2") (pinfunction "2_2") (pintype "passive"))
      (node (ref "U13") (pin "13") (pinfunction "OUTNL_13") (pintype "passive"))
    )
    (net (code "107") (name "Net-(U13-OUTNR)") (class "Default")
      (node (ref "C122") (pin "1") (pinfunction "1_1") (pintype "passive"))
      (node (ref "L16") (pin "2") (pinfunction "2_2") (pintype "passive"))
      (node (ref "U13") (pin "12") (pinfunction "OUTNR_12") (pintype "passive"))
    )
    (net (code "108") (name "Net-(U13-OUTPL)") (class "Default")
      (node (ref "C104") (pin "1") (pinfunction "1_1") (pintype "passive"))
      (node (ref "L11") (pin "2") (pinfunction "2_2") (pintype "passive"))
      (node (ref "U13") (pin "15") (pinfunction "OUTPL_15") (pintype "passive"))
    )
    (net (code "109") (name "Net-(U13-OUTPR)") (class "Default")
      (node (ref "C136") (pin "1") (pinfunction "1_1") (pintype "passive"))
      (node (ref "L18") (pin "2") (pinfunction "2_2") (pintype "passive"))
      (node (ref "U13") (pin "10") (pinfunction "OUTPR_10") (pintype "passive"))
    )
    (net (code "110") (name "Net-(U13-PSPR)") (class "Default")
      (node (ref "C136") (pin "2") (pinfunction "2_2") (pintype "passive"))
      (node (ref "U13") (pin "9") (pinfunction "PSPR_9") (pintype "passive"))
    )
    (net (code "111") (name "Net-(U14-BSMNR)") (class "Default")
      (node (ref "C124") (pin "2") (pinfunction "2_2") (pintype "passive"))
      (node (ref "U14") (pin "11") (pinfunction "BSMNR_11") (pintype "passive"))
    )
    (net (code "112") (name "Net-(U14-BSNL)") (class "Default")
      (node (ref "C112") (pin "2") (pinfunction "2_2") (pintype "passive"))
      (node (ref "U14") (pin "14") (pinfunction "BSNL_14") (pintype "passive"))
    )
    (net (code "113") (name "Net-(U14-BSPL)") (class "Default")
      (node (ref "C105") (pin "2") (pinfunction "2_2") (pintype "passive"))
      (node (ref "U14") (pin "16") (pinfunction "BSPL_16") (pintype "passive"))
    )
    (net (code "114") (name "Net-(U14-GVDD)") (class "Default")
      (node (ref "C121") (pin "2") (pinfunction "2_2") (pintype "passive"))
      (node (ref "U14") (pin "5") (pinfunction "GVDD_5") (pintype "passive"))
    )
    (net (code "115") (name "Net-(U14-INNL)") (class "Default")
      (node (ref "R73") (pin "2") (pinfunction "2_2") (pintype "passive"))
      (node (ref "U14") (pin "4") (pinfunction "INNL_4") (pintype "passive"))
    )
    (net (code "116") (name "Net-(U14-INNR)") (class "Default")
      (node (ref "R75") (pin "2") (pinfunction "2_2") (pintype "passive"))
      (node (ref "U14") (pin "6") (pinfunction "INNR_6") (pintype "passive"))
    )
    (net (code "117") (name "Net-(U14-INPL)") (class "Default")
      (node (ref "R71") (pin "2") (pinfunction "2_2") (pintype "passive"))
      (node (ref "U14") (pin "3") (pinfunction "INPL_3") (pintype "passive"))
    )
    (net (code "118") (name "Net-(U14-INPR)") (class "Default")
      (node (ref "R79") (pin "2") (pinfunction "2_2") (pintype "passive"))
      (node (ref "U14") (pin "7") (pinfunction "INPR_7") (pintype "passive"))
    )
    (net (code "119") (name "Net-(U14-OUTNL)") (class "Default")
      (node (ref "C112") (pin "1") (pinfunction "1_1") (pintype "passive"))
      (node (ref "L15") (pin "2") (pinfunction "2_2") (pintype "passive"))
      (node (ref "U14") (pin "13") (pinfunction "OUTNL_13") (pintype "passive"))
    )
    (net (code "120") (name "Net-(U14-OUTNR)") (class "Default")
      (node (ref "C124") (pin "1") (pinfunction "1_1") (pintype "passive"))
      (node (ref "L17") (pin "2") (pinfunction "2_2") (pintype "passive"))
      (node (ref "U14") (pin "12") (pinfunction "OUTNR_12") (pintype "passive"))
    )
    (net (code "121") (name "Net-(U14-OUTPL)") (class "Default")
      (node (ref "C105") (pin "1") (pinfunction "1_1") (pintype "passive"))
      (node (ref "L13") (pin "2") (pinfunction "2_2") (pintype "passive"))
      (node (ref "U14") (pin "15") (pinfunction "OUTPL_15") (pintype "passive"))
    )
    (net (code "122") (name "Net-(U14-OUTPR)") (class "Default")
      (node (ref "C137") (pin "1") (pinfunction "1_1") (pintype "passive"))
      (node (ref "L19") (pin "2") (pinfunction "2_2") (pintype "passive"))
      (node (ref "U14") (pin "10") (pinfunction "OUTPR_10") (pintype "passive"))
    )
    (net (code "123") (name "Net-(U14-PSPR)") (class "Default")
      (node (ref "C137") (pin "2") (pinfunction "2_2") (pintype "passive"))
      (node (ref "U14") (pin "9") (pinfunction "PSPR_9") (pintype "passive"))
    )
    (net (code "124") (name "Net-(U15-BSMNR)") (class "Default")
      (node (ref "C165") (pin "2") (pinfunction "2_2") (pintype "passive"))
      (node (ref "U15") (pin "11") (pinfunction "BSMNR_11") (pintype "passive"))
      (node (ref "U15") (pin "9") (pinfunction "PSPR_9") (pintype "passive"))
    )
    (net (code "125") (name "Net-(U15-BSNL)") (class "Default")
      (node (ref "C151") (pin "2") (pinfunction "2_2") (pintype "passive"))
      (node (ref "U15") (pin "14") (pinfunction "BSNL_14") (pintype "passive"))
      (node (ref "U15") (pin "16") (pinfunction "BSPL_16") (pintype "passive"))
    )
    (net (code "126") (name "Net-(U15-GVDD)") (class "Default")
      (node (ref "C155") (pin "2") (pinfunction "2_2") (pintype "passive"))
      (node (ref "U15") (pin "5") (pinfunction "GVDD_5") (pintype "passive"))
    )
    (net (code "127") (name "Net-(U15-INNR)") (class "Default")
      (node (ref "R84") (pin "2") (pinfunction "2_2") (pintype "passive"))
      (node (ref "U15") (pin "6") (pinfunction "INNR_6") (pintype "passive"))
    )
    (net (code "128") (name "Net-(U15-INPR)") (class "Default")
      (node (ref "R86") (pin "2") (pinfunction "2_2") (pintype "passive"))
      (node (ref "U15") (pin "7") (pinfunction "INPR_7") (pintype "passive"))
    )
    (net (code "129") (name "Net-(U15-OUTNL)") (class "Default")
      (node (ref "C151") (pin "1") (pinfunction "1_1") (pintype "passive"))
      (node (ref "L20") (pin "2") (pinfunction "2_2") (pintype "passive"))
      (node (ref "U15") (pin "13") (pinfunction "OUTNL_13") (pintype "passive"))
      (node (ref "U15") (pin "15") (pinfunction "OUTPL_15") (pintype "passive"))
    )
    (net (code "130") (name "Net-(U15-OUTNR)") (class "Default")
      (node (ref "C165") (pin "1") (pinfunction "1_1") (pintype "passive"))
      (node (ref "L22") (pin "2") (pinfunction "2_2") (pintype "passive"))
      (node (ref "U15") (pin "10") (pinfunction "OUTPR_10") (pintype "passive"))
      (node (ref "U15") (pin "12") (pinfunction "OUTNR_12") (pintype "passive"))
    )
    (net (code "131") (name "Net-(U16-BSMNR)") (class "Default")
      (node (ref "C166") (pin "2") (pinfunction "2_2") (pintype "passive"))
      (node (ref "U16") (pin "11") (pinfunction "BSMNR_11") (pintype "passive"))
      (node (ref "U16") (pin "9") (pinfunction "PSPR_9") (pintype "passive"))
    )
    (net (code "132") (name "Net-(U16-BSNL)") (class "Default")
      (node (ref "C152") (pin "2") (pinfunction "2_2") (pintype "passive"))
      (node (ref "U16") (pin "14") (pinfunction "BSNL_14") (pintype "passive"))
      (node (ref "U16") (pin "16") (pinfunction "BSPL_16") (pintype "passive"))
    )
    (net (code "133") (name "Net-(U16-GVDD)") (class "Default")
      (node (ref "C157") (pin "2") (pinfunction "2_2") (pintype "passive"))
      (node (ref "U16") (pin "5") (pinfunction "GVDD_5") (pintype "passive"))
    )
    (net (code "134") (name "Net-(U16-INNR)") (class "Default")
      (node (ref "R85") (pin "2") (pinfunction "2_2") (pintype "passive"))
      (node (ref "U16") (pin "6") (pinfunction "INNR_6") (pintype "passive"))
    )
    (net (code "135") (name "Net-(U16-INPR)") (class "Default")
      (node (ref "R87") (pin "2") (pinfunction "2_2") (pintype "passive"))
      (node (ref "U16") (pin "7") (pinfunction "INPR_7") (pintype "passive"))
    )
    (net (code "136") (name "Net-(U16-OUTNL)") (class "Default")
      (node (ref "C152") (pin "1") (pinfunction "1_1") (pintype "passive"))
      (node (ref "L21") (pin "2") (pinfunction "2_2") (pintype "passive"))
      (node (ref "U16") (pin "13") (pinfunction "OUTNL_13") (pintype "passive"))
      (node (ref "U16") (pin "15") (pinfunction "OUTPL_15") (pintype "passive"))
    )
    (net (code "137") (name "Net-(U16-OUTNR)") (class "Default")
      (node (ref "C166") (pin "1") (pinfunction "1_1") (pintype "passive"))
      (node (ref "L23") (pin "2") (pinfunction "2_2") (pintype "passive"))
      (node (ref "U16") (pin "10") (pinfunction "OUTPR_10") (pintype "passive"))
      (node (ref "U16") (pin "12") (pinfunction "OUTNR_12") (pintype "passive"))
    )
    (net (code "138") (name "VCC") (class "Default")
      (node (ref "C103") (pin "1") (pinfunction "POS_1") (pintype "passive"))
      (node (ref "C12") (pin "2") (pinfunction "2_2") (pintype "passive"))
      (node (ref "C13") (pin "1") (pinfunction "1_1") (pintype "passive"))
      (node (ref "C138") (pin "1") (pinfunction "POS_1") (pintype "passive"))
      (node (ref "C139") (pin "2") (pinfunction "2_2") (pintype "passive"))
      (node (ref "C14") (pin "1") (pinfunction "POS_1") (pintype "passive"))
      (node (ref "C140") (pin "1") (pinfunction "1_1") (pintype "passive"))
      (node (ref "C141") (pin "1") (pinfunction "POS_1") (pintype "passive"))
      (node (ref "C143") (pin "2") (pinfunction "2_2") (pintype "passive"))
      (node (ref "C144") (pin "1") (pinfunction "1_1") (pintype "passive"))
      (node (ref "C145") (pin "1") (pinfunction "1_1") (pintype "passive"))
      (node (ref "C146") (pin "2") (pinfunction "2_2") (pintype "passive"))
      (node (ref "C147") (pin "1") (pinfunction "POS_1") (pintype "passive"))
      (node (ref "C148") (pin "1") (pinfunction "1_1") (pintype "passive"))
      (node (ref "C149") (pin "2") (pinfunction "2_2") (pintype "passive"))
      (node (ref "C150") (pin "1") (pinfunction "POS_1") (pintype "passive"))
      (node (ref "C16") (pin "2") (pinfunction "2_2") (pintype "passive"))
      (node (ref "C167") (pin "1") (pinfunction "POS_1") (pintype "passive"))
      (node (ref "C168") (pin "2") (pinfunction "2_2") (pintype "passive"))
      (node (ref "C169") (pin "1") (pinfunction "1_1") (pintype "passive"))
      (node (ref "C170") (pin "1") (pinfunction "POS_1") (pintype "passive"))
      (node (ref "C171") (pin "2") (pinfunction "2_2") (pintype "passive"))
      (node (ref "C172") (pin "1") (pinfunction "1_1") (pintype "passive"))
      (node (ref "C22") (pin "1") (pinfunction "1_1") (pintype "passive"))
      (node (ref "C24") (pin "1") (pinfunction "1_1") (pintype "passive"))
      (node (ref "C25") (pin "1") (pinfunction "POS_1") (pintype "passive"))
      (node (ref "C26") (pin "2") (pinfunction "2_2") (pintype "passive"))
      (node (ref "C27") (pin "1") (pinfunction "POS_1") (pintype "passive"))
      (node (ref "C28") (pin "1") (pinfunction "POS_1") (pintype "passive"))
      (node (ref "C53") (pin "1") (pinfunction "POS_1") (pintype "passive"))
      (node (ref "C55") (pin "2") (pinfunction "2_2") (pintype "passive"))
      (node (ref "C56") (pin "1") (pinfunction "1_1") (pintype "passive"))
      (node (ref "C6") (pin "1") (pinfunction "1_1") (pintype "passive"))
      (node (ref "C84") (pin "1") (pinfunction "1_1") (pintype "passive"))
      (node (ref "C85") (pin "2") (pinfunction "2_2") (pintype "passive"))
      (node (ref "C86") (pin "1") (pinfunction "POS_1") (pintype "passive"))
      (node (ref "C87") (pin "1") (pinfunction "1_1") (pintype "passive"))
      (node (ref "C88") (pin "2") (pinfunction "2_2") (pintype "passive"))
      (node (ref "J5") (pin "1") (pinfunction "1_1") (pintype "passive"))
      (node (ref "U13") (pin "1") (pinfunction "PVCC_1") (pintype "passive"))
      (node (ref "U13") (pin "8") (pinfunction "PVCC_8") (pintype "passive"))
      (node (ref "U14") (pin "1") (pinfunction "PVCC_1") (pintype "passive"))
      (node (ref "U14") (pin "8") (pinfunction "PVCC_8") (pintype "passive"))
      (node (ref "U15") (pin "1") (pinfunction "PVCC_1") (pintype "passive"))
      (node (ref "U15") (pin "8") (pinfunction "PVCC_8") (pintype "passive"))
      (node (ref "U16") (pin "1") (pinfunction "PVCC_1") (pintype "passive"))
      (node (ref "U16") (pin "8") (pinfunction "PVCC_8") (pintype "passive"))
      (node (ref "U5") (pin "1") (pinfunction "PVCC_1") (pintype "passive"))
      (node (ref "U5") (pin "8") (pinfunction "PVCC_8") (pintype "passive"))
      (node (ref "U7") (pin "1") (pinfunction "PVCC_1") (pintype "passive"))
      (node (ref "U7") (pin "8") (pinfunction "PVCC_8") (pintype "passive"))
    )
    (net (code "139") (name "unconnected-(U10-+-Pad1)") (class "Default")
      (node (ref "U10") (pin "1") (pinfunction "+_1") (pintype "passive"))
    )
    (net (code "140") (name "unconnected-(U10---Pad2)") (class "Default")
      (node (ref "U10") (pin "2") (pinfunction "-_2") (pintype "passive"))
    )
  )
)
